# remote_v0_9_a8132eb9.net
KiCad netlist of a schematic drawn in EAGLE
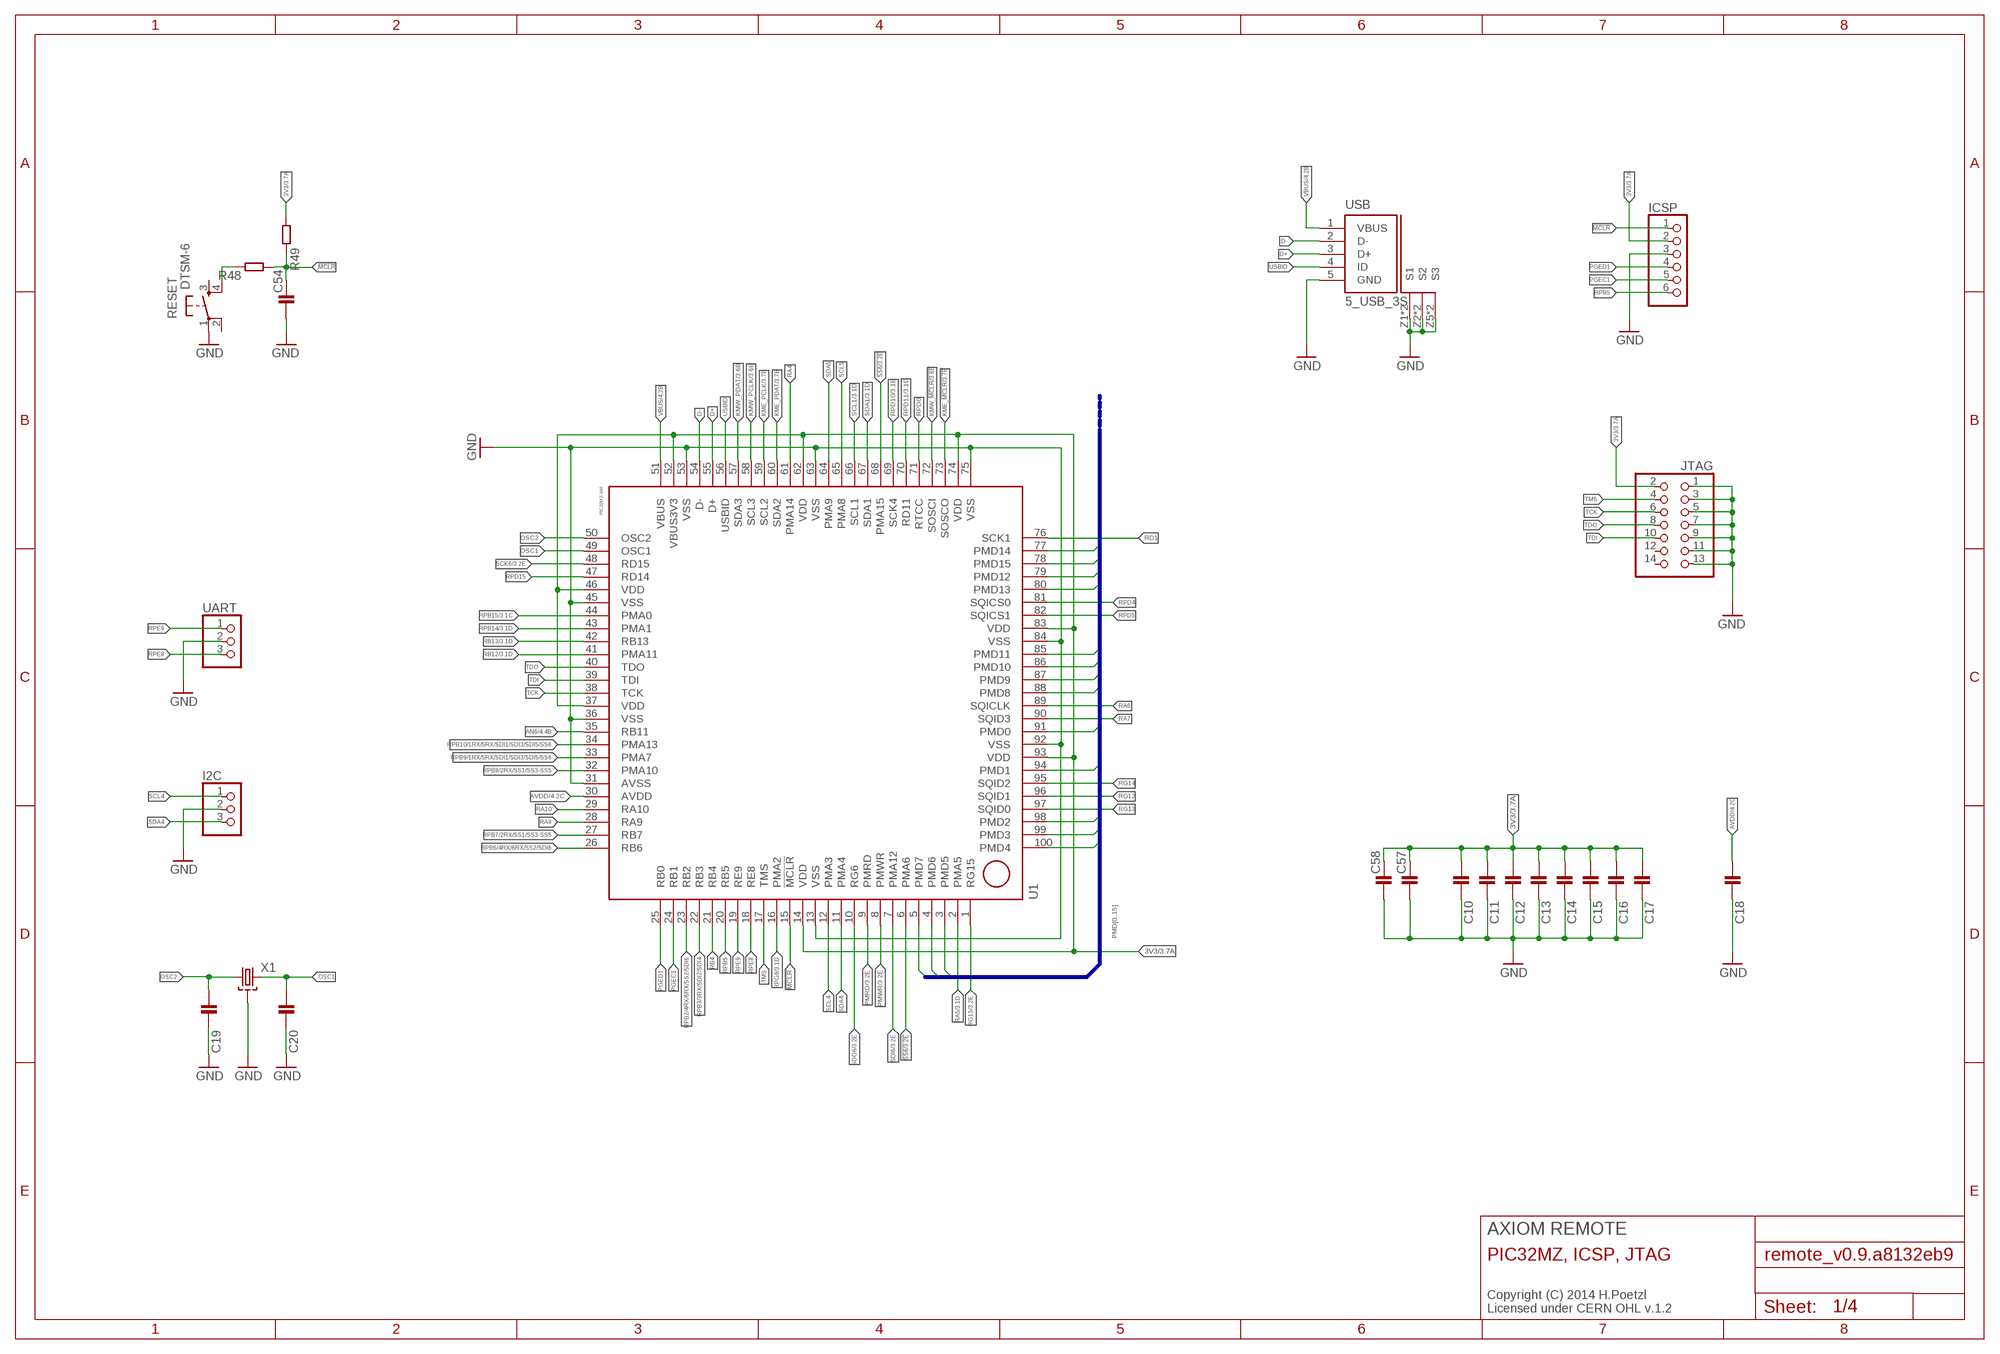
[diagram p0: schematic, sheet 1]
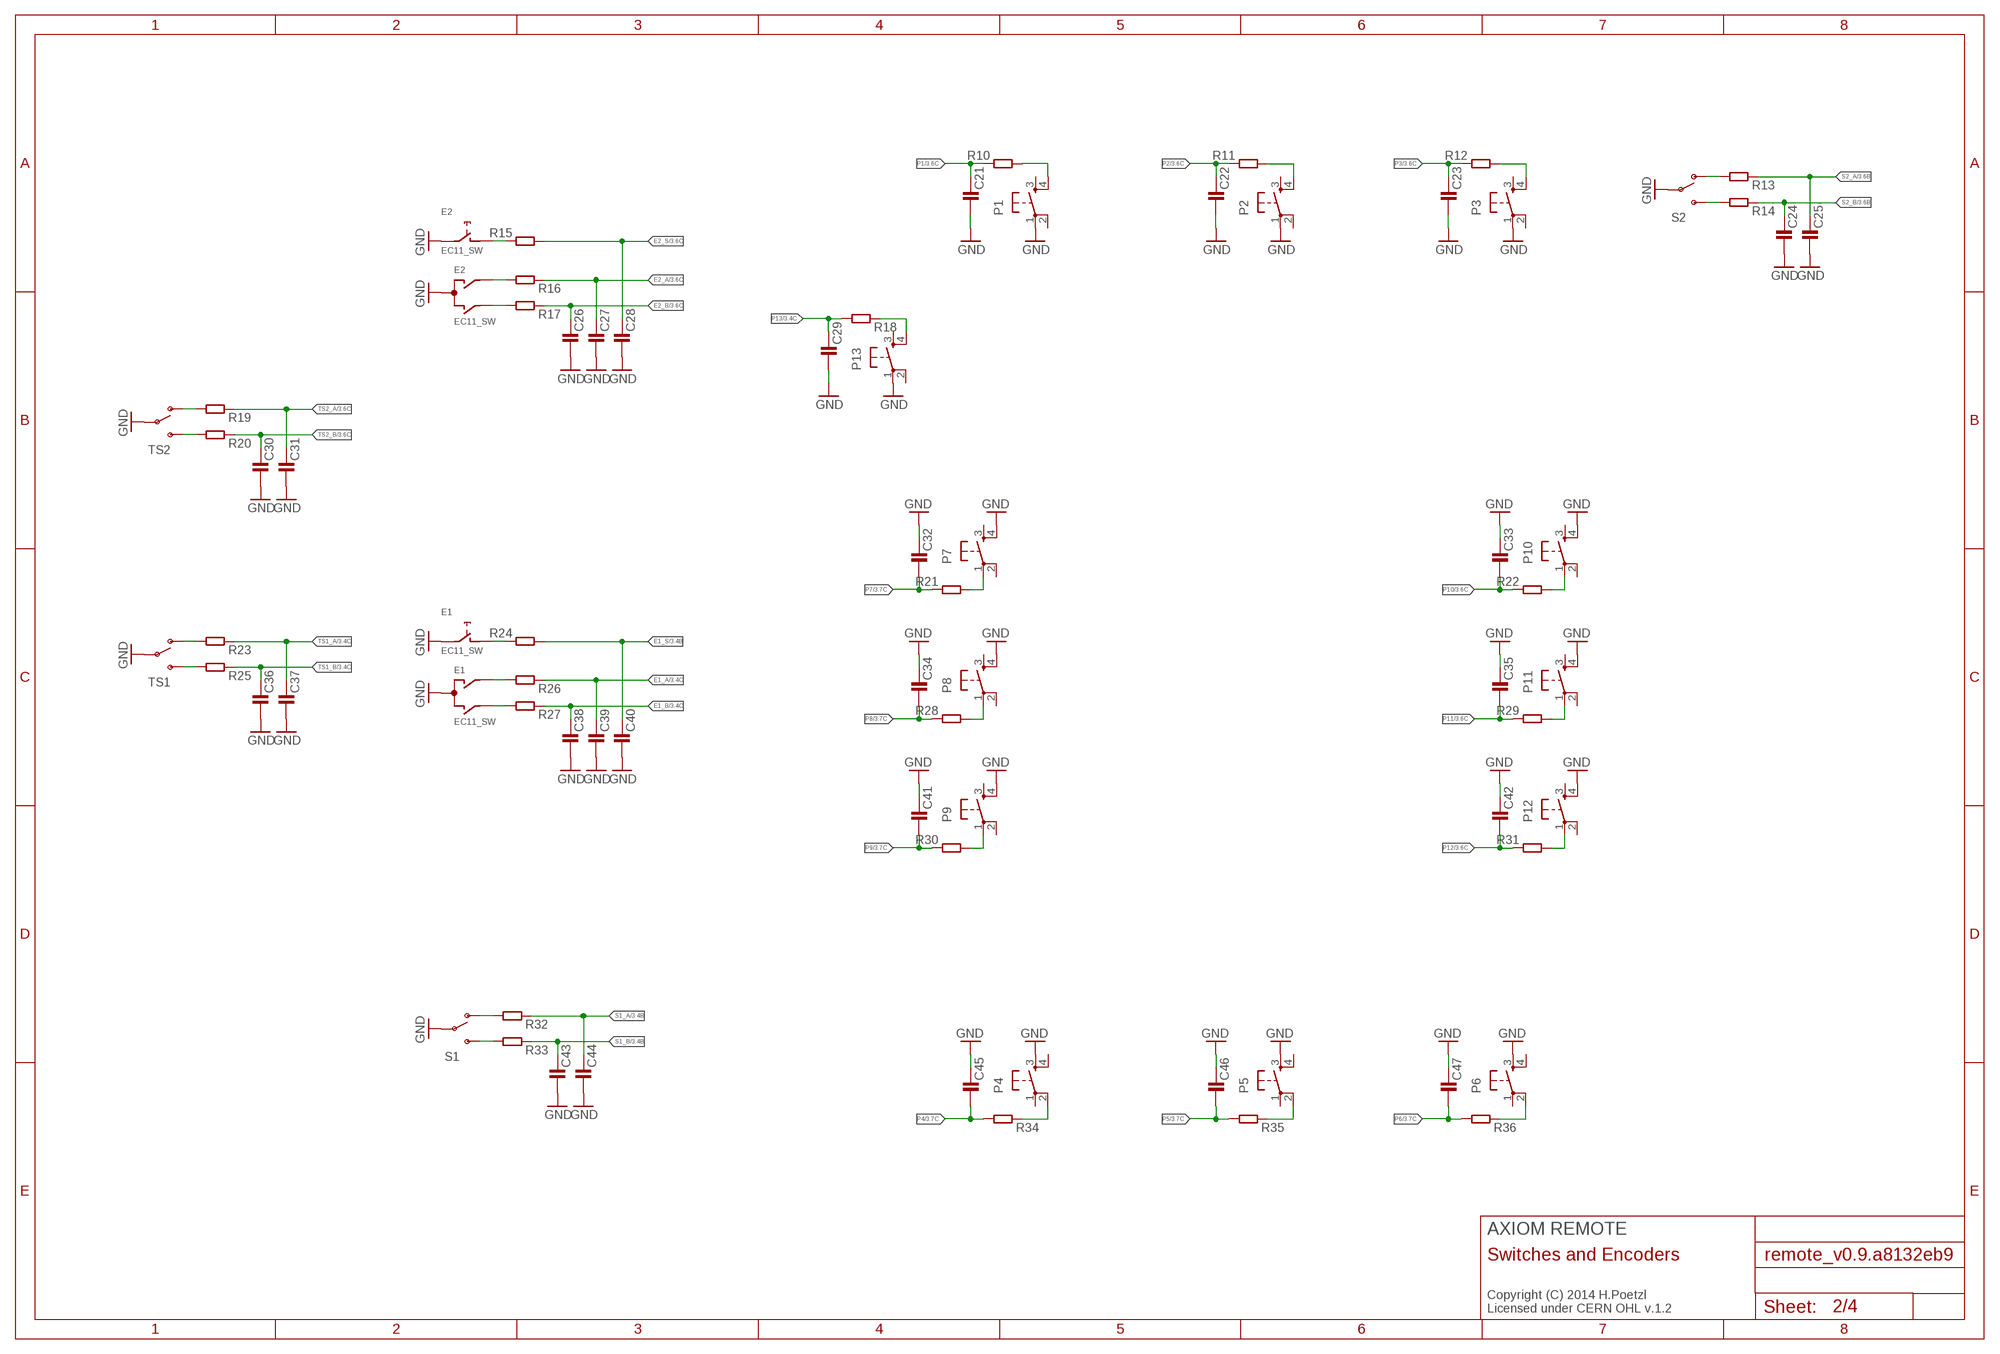
[diagram p1: schematic, sheet 2]
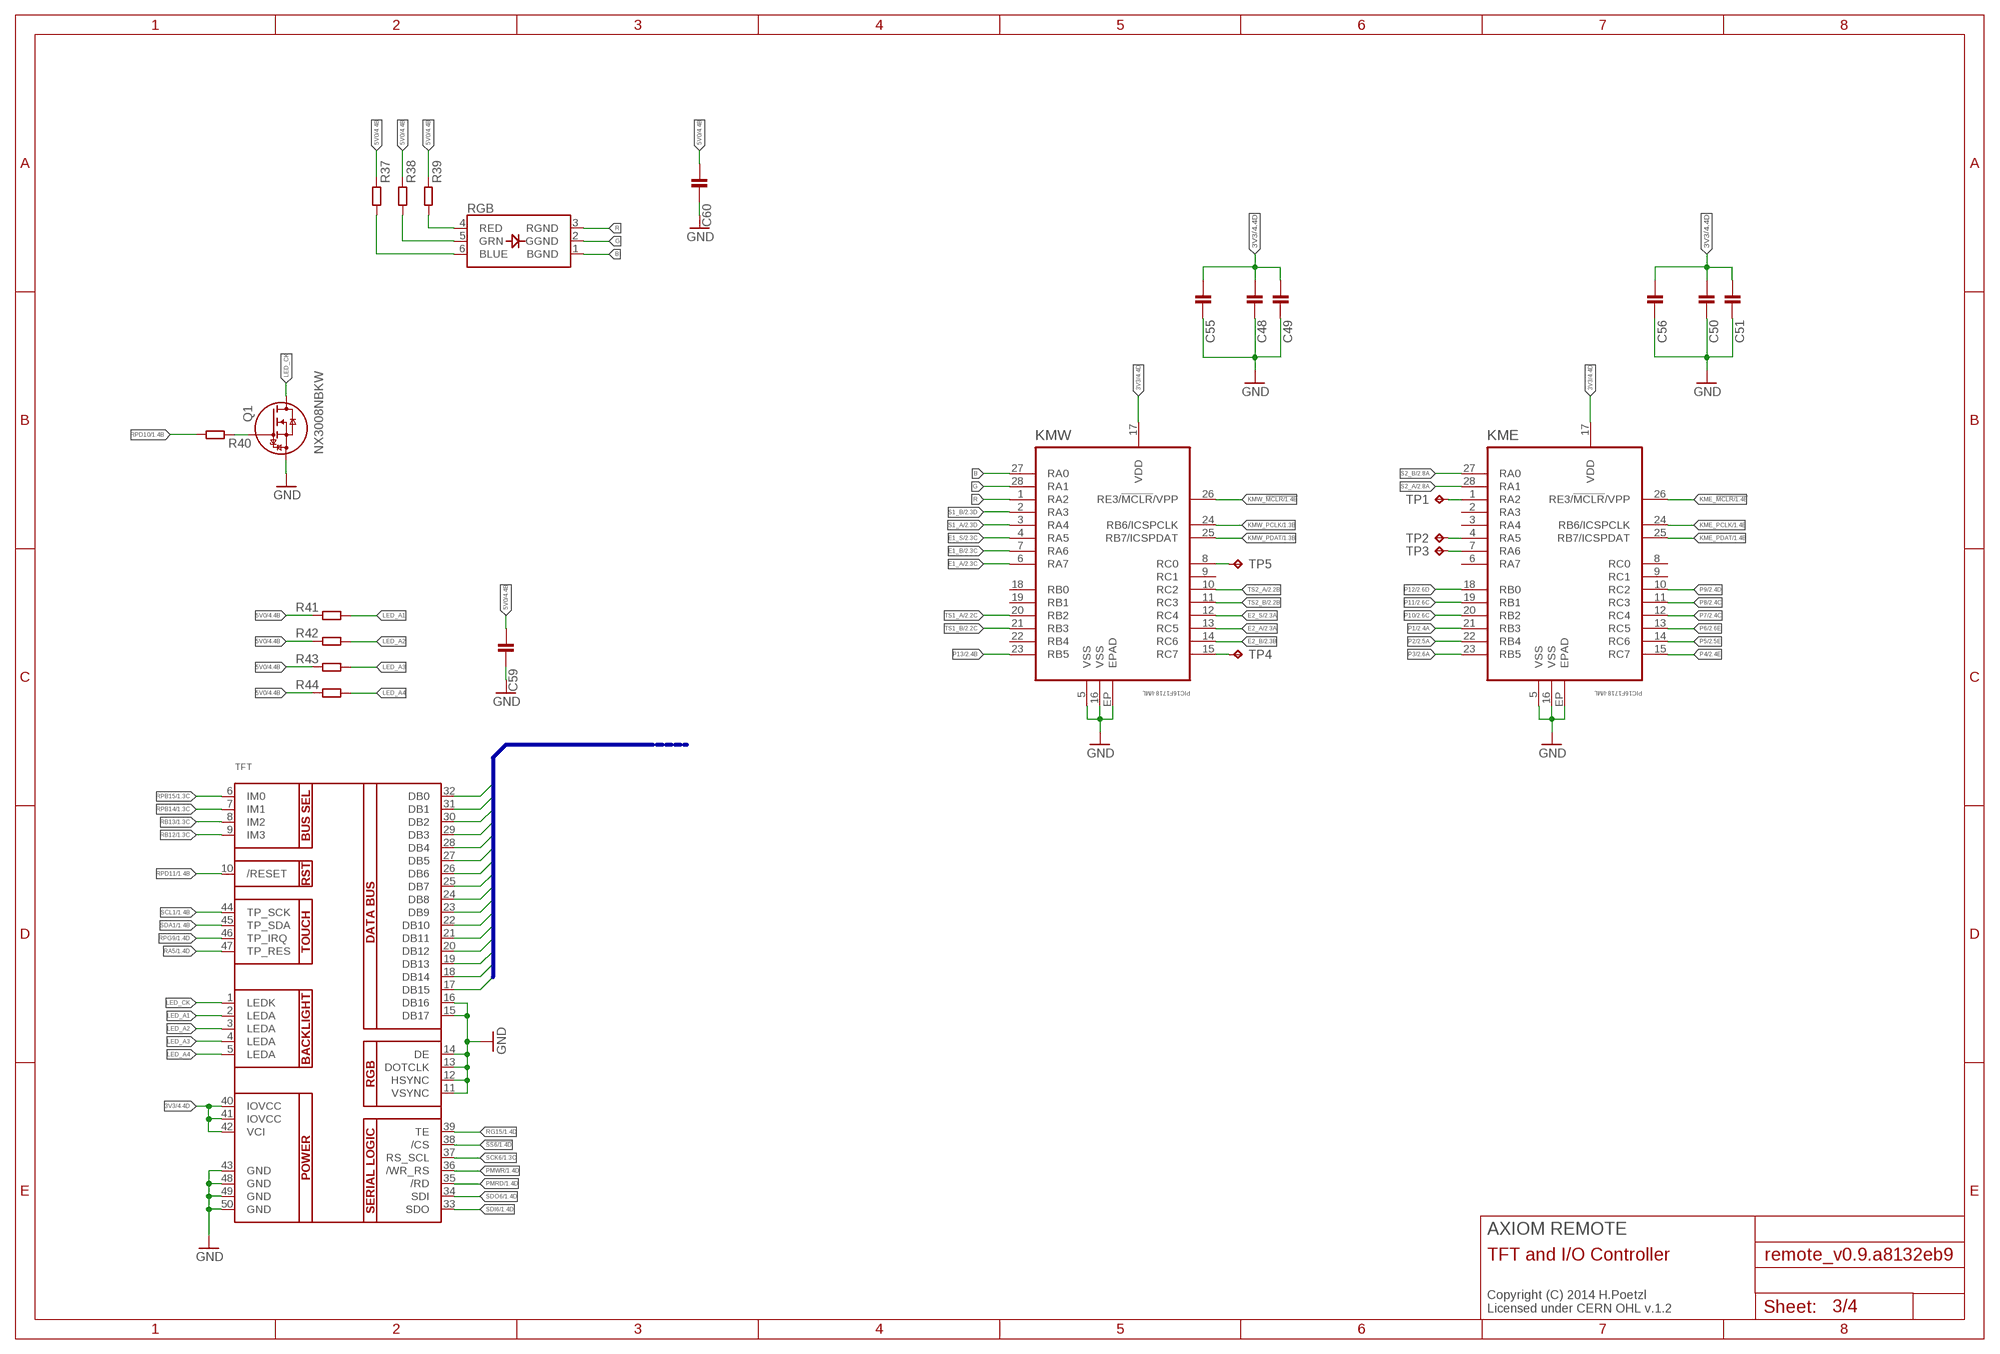
[diagram p2: schematic, sheet 3]
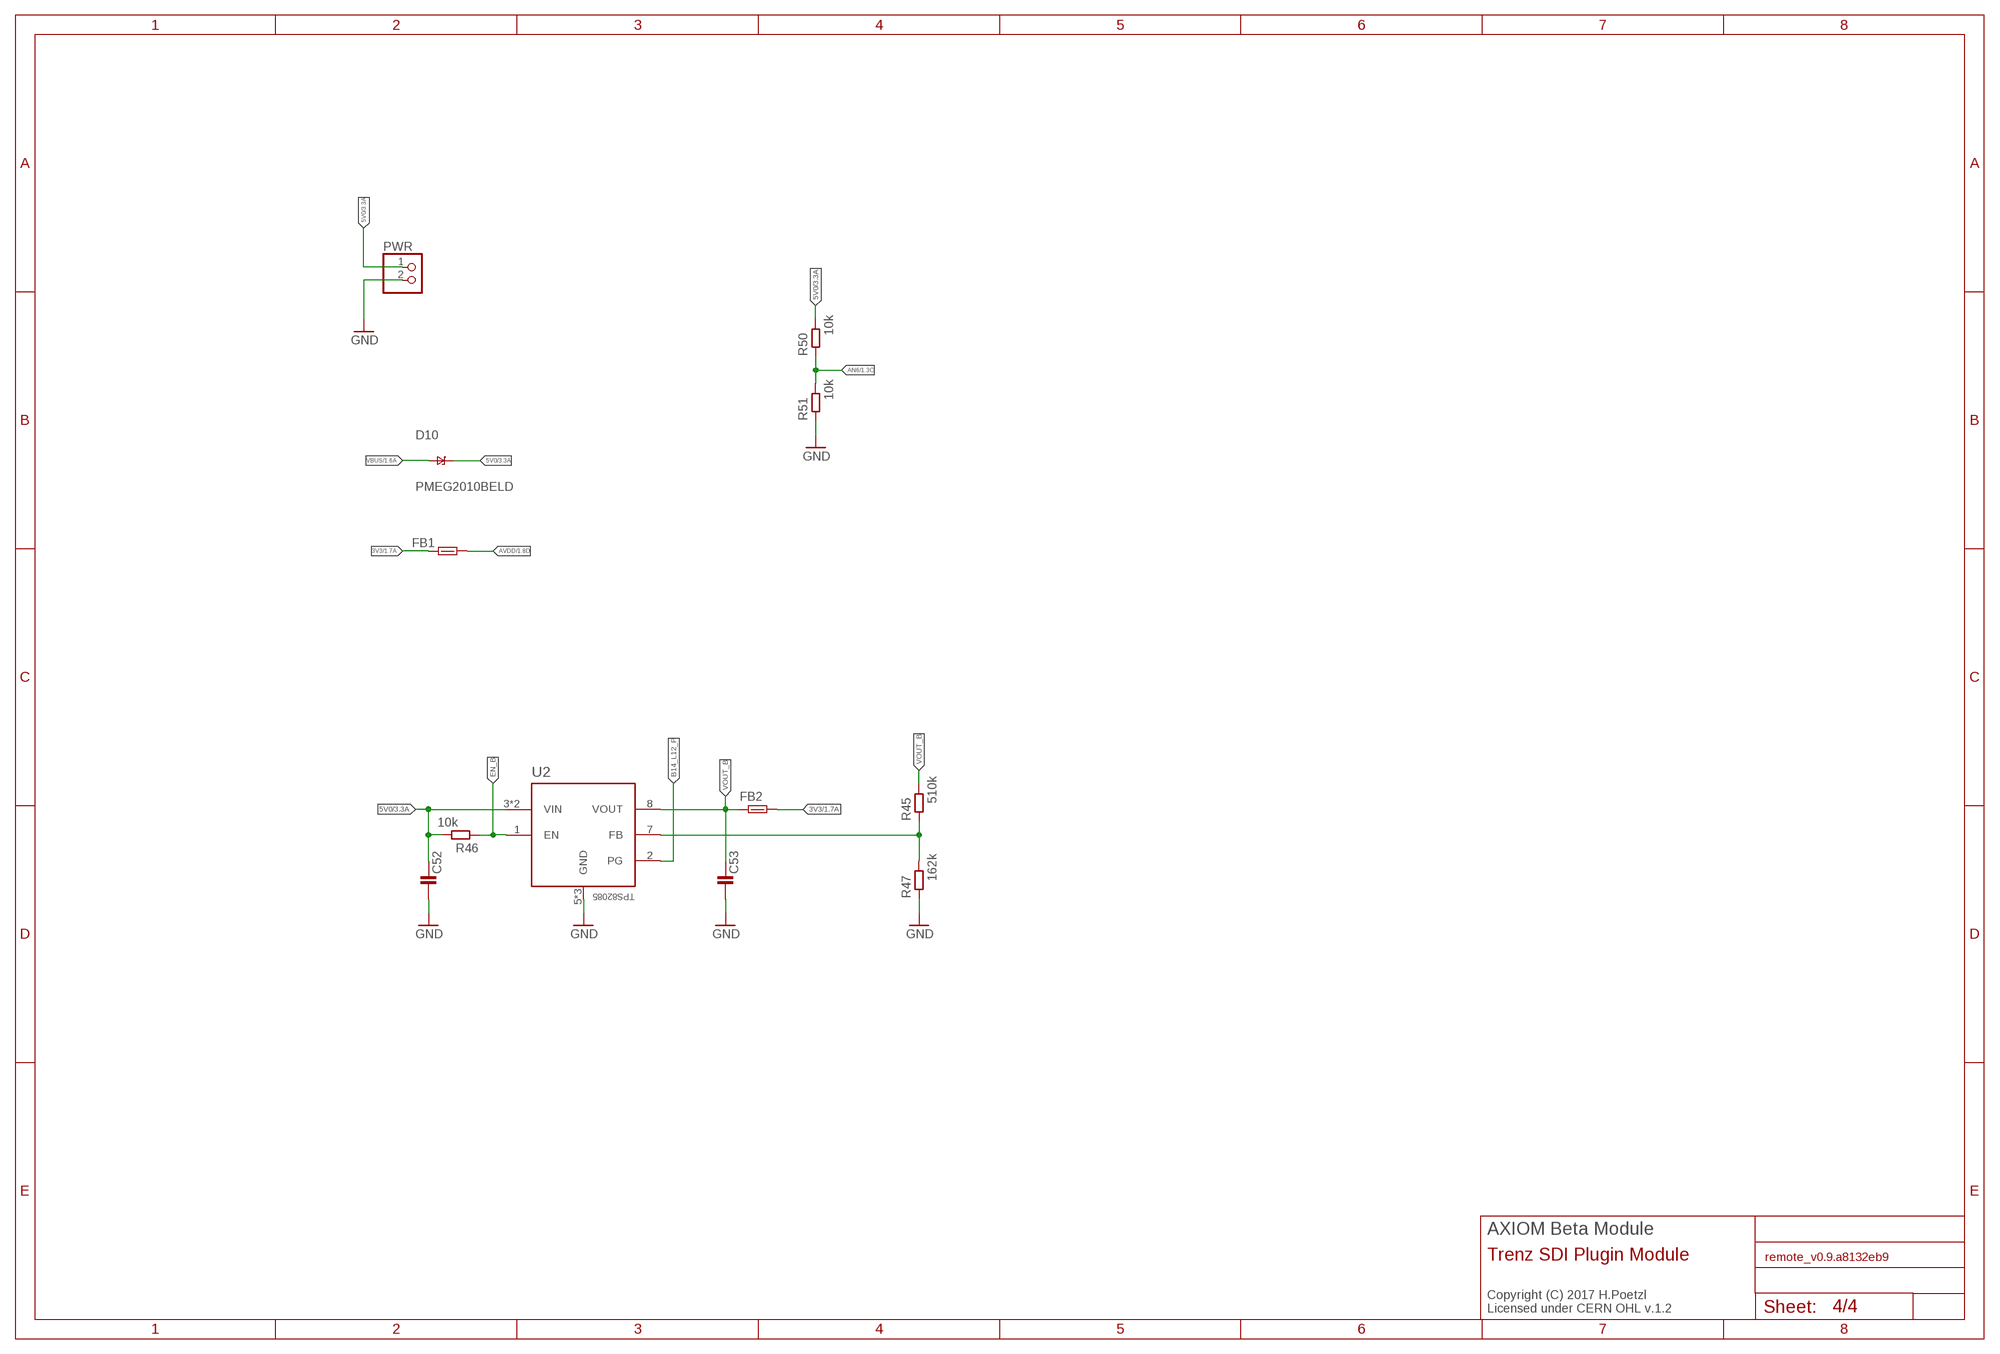
[diagram p3: schematic, sheet 4]

(export (version "E")
  (design (tool "Eeschema 10.0.6"))
  (components
    (comp (ref "C52")
      (value "C0603-C")
      (footprint "eagle-import:0603-C")
      (libsource (lib "eagle-import") (part "C0603-C"))
    )
    (comp (ref "C53")
      (value "C0603-C")
      (footprint "eagle-import:0603-C")
      (libsource (lib "eagle-import") (part "C0603-C"))
    )
    (comp (ref "D10")
      (value "PMEG2010BELD")
      (footprint "eagle-import:DFN1006D-2")
      (libsource (lib "eagle-import") (part "PMEG2010BELD"))
    )
    (comp (ref "FB1")
      (value "FB0402-C")
      (footprint "eagle-import:0402-C")
      (libsource (lib "eagle-import") (part "FB0402-C"))
    )
    (comp (ref "FB2")
      (value "FB0603-C")
      (footprint "eagle-import:0603-C")
      (libsource (lib "eagle-import") (part "FB0603-C"))
    )
    (comp (ref "PWR")
      (value "PINHD-1X02_2.54-90°")
      (footprint "eagle-import:1X02_90")
      (libsource (lib "eagle-import") (part "PINHD-1X02_2.54-90°"))
    )
    (comp (ref "R45")
      (value "510k")
      (footprint "eagle-import:0201-C")
      (libsource (lib "eagle-import") (part "R0201-C"))
    )
    (comp (ref "R46")
      (value "10k")
      (footprint "eagle-import:0201-C")
      (libsource (lib "eagle-import") (part "R0201-C"))
    )
    (comp (ref "R47")
      (value "162k")
      (footprint "eagle-import:0201-C")
      (libsource (lib "eagle-import") (part "R0201-C"))
    )
    (comp (ref "R50")
      (value "10k")
      (footprint "eagle-import:0402-C")
      (libsource (lib "eagle-import") (part "R0402-C"))
    )
    (comp (ref "R51")
      (value "10k")
      (footprint "eagle-import:0402-C")
      (libsource (lib "eagle-import") (part "R0402-C"))
    )
    (comp (ref "U2")
      (value "TPS82085")
      (footprint "eagle-import:MICROSIP")
      (libsource (lib "eagle-import") (part "TPS82085"))
    )
    (comp (ref "C10")
      (value "100n")
      (footprint "eagle-import:0402-C")
      (libsource (lib "eagle-import") (part "C0402-C"))
    )
    (comp (ref "C11")
      (value "100n")
      (footprint "eagle-import:0402-C")
      (libsource (lib "eagle-import") (part "C0402-C"))
    )
    (comp (ref "C12")
      (value "100n")
      (footprint "eagle-import:0402-C")
      (libsource (lib "eagle-import") (part "C0402-C"))
    )
    (comp (ref "C13")
      (value "100n")
      (footprint "eagle-import:0402-C")
      (libsource (lib "eagle-import") (part "C0402-C"))
    )
    (comp (ref "C14")
      (value "100n")
      (footprint "eagle-import:0402-C")
      (libsource (lib "eagle-import") (part "C0402-C"))
    )
    (comp (ref "C15")
      (value "100n")
      (footprint "eagle-import:0402-C")
      (libsource (lib "eagle-import") (part "C0402-C"))
    )
    (comp (ref "C16")
      (value "100n")
      (footprint "eagle-import:0402-C")
      (libsource (lib "eagle-import") (part "C0402-C"))
    )
    (comp (ref "C17")
      (value "100n")
      (footprint "eagle-import:0402-C")
      (libsource (lib "eagle-import") (part "C0402-C"))
    )
    (comp (ref "C18")
      (value "100n")
      (footprint "eagle-import:0402-C")
      (libsource (lib "eagle-import") (part "C0402-C"))
    )
    (comp (ref "C19")
      (value "100n")
      (footprint "eagle-import:0402-C")
      (libsource (lib "eagle-import") (part "C0402-C"))
    )
    (comp (ref "C20")
      (value "100n")
      (footprint "eagle-import:0402-C")
      (libsource (lib "eagle-import") (part "C0402-C"))
    )
    (comp (ref "C54")
      (value "C0402-C")
      (footprint "eagle-import:0402-C")
      (libsource (lib "eagle-import") (part "C0402-C"))
    )
    (comp (ref "C57")
      (value "C0805-C")
      (footprint "eagle-import:0805-C")
      (libsource (lib "eagle-import") (part "C0805-C"))
    )
    (comp (ref "C58")
      (value "C0805-C")
      (footprint "eagle-import:0805-C")
      (libsource (lib "eagle-import") (part "C0805-C"))
    )
    (comp (ref "I2C")
      (value "PINHD-1X03_2.54-90°")
      (footprint "eagle-import:1X03_90")
      (libsource (lib "eagle-import") (part "PINHD-1X03_2.54-90°"))
    )
    (comp (ref "ICSP")
      (value "PINHD-1X6/90")
      (footprint "eagle-import:1X06_90")
      (libsource (lib "eagle-import") (part "PINHD-1X6/90"))
    )
    (comp (ref "JTAG")
      (value "PINHD-2X07_2.00")
      (footprint "eagle-import:2X07M")
      (libsource (lib "eagle-import") (part "PINHD-2X07_2.00"))
    )
    (comp (ref "R48")
      (value "R0402-C")
      (footprint "eagle-import:0402-C")
      (libsource (lib "eagle-import") (part "R0402-C"))
    )
    (comp (ref "R49")
      (value "R0402-C")
      (footprint "eagle-import:0402-C")
      (libsource (lib "eagle-import") (part "R0402-C"))
    )
    (comp (ref "RESET")
      (value "DTSM-6")
      (footprint "eagle-import:3X4MM")
      (libsource (lib "eagle-import") (part "DTSM-6"))
    )
    (comp (ref "U1")
      (value "PIC32MZ-100")
      (footprint "eagle-import:QFP40P1400X1400X120-100N")
      (libsource (lib "eagle-import") (part "PIC32MZ-100"))
    )
    (comp (ref "UART")
      (value "PINHD-1X03_2.54-90°")
      (footprint "eagle-import:1X03_90")
      (libsource (lib "eagle-import") (part "PINHD-1X03_2.54-90°"))
    )
    (comp (ref "USB")
      (value "5_USB_3S")
      (footprint "eagle-import:MICRO-AB-H-SMT")
      (libsource (lib "eagle-import") (part "5_USB_3S"))
    )
    (comp (ref "X1")
      (value "SMD-4P-2G-2.0X1.6")
      (footprint "eagle-import:2.0X1.6")
      (libsource (lib "eagle-import") (part "SMD-4P-2G-2.0X1.6"))
    )
    (comp (ref "C21")
      (value "C0402-C")
      (footprint "eagle-import:0402-C")
      (libsource (lib "eagle-import") (part "C0402-C"))
    )
    (comp (ref "C22")
      (value "C0402-C")
      (footprint "eagle-import:0402-C")
      (libsource (lib "eagle-import") (part "C0402-C"))
    )
    (comp (ref "C23")
      (value "C0402-C")
      (footprint "eagle-import:0402-C")
      (libsource (lib "eagle-import") (part "C0402-C"))
    )
    (comp (ref "C24")
      (value "C0402-C")
      (footprint "eagle-import:0402-C")
      (libsource (lib "eagle-import") (part "C0402-C"))
    )
    (comp (ref "C25")
      (value "C0402-C")
      (footprint "eagle-import:0402-C")
      (libsource (lib "eagle-import") (part "C0402-C"))
    )
    (comp (ref "C26")
      (value "C0402-C")
      (footprint "eagle-import:0402-C")
      (libsource (lib "eagle-import") (part "C0402-C"))
    )
    (comp (ref "C27")
      (value "C0402-C")
      (footprint "eagle-import:0402-C")
      (libsource (lib "eagle-import") (part "C0402-C"))
    )
    (comp (ref "C28")
      (value "C0402-C")
      (footprint "eagle-import:0402-C")
      (libsource (lib "eagle-import") (part "C0402-C"))
    )
    (comp (ref "C29")
      (value "C0402-C")
      (footprint "eagle-import:0402-C")
      (libsource (lib "eagle-import") (part "C0402-C"))
    )
    (comp (ref "C30")
      (value "C0402-C")
      (footprint "eagle-import:0402-C")
      (libsource (lib "eagle-import") (part "C0402-C"))
    )
    (comp (ref "C31")
      (value "C0402-C")
      (footprint "eagle-import:0402-C")
      (libsource (lib "eagle-import") (part "C0402-C"))
    )
    (comp (ref "C32")
      (value "C0402-C")
      (footprint "eagle-import:0402-C")
      (libsource (lib "eagle-import") (part "C0402-C"))
    )
    (comp (ref "C33")
      (value "C0402-C")
      (footprint "eagle-import:0402-C")
      (libsource (lib "eagle-import") (part "C0402-C"))
    )
    (comp (ref "C34")
      (value "C0402-C")
      (footprint "eagle-import:0402-C")
      (libsource (lib "eagle-import") (part "C0402-C"))
    )
    (comp (ref "C35")
      (value "C0402-C")
      (footprint "eagle-import:0402-C")
      (libsource (lib "eagle-import") (part "C0402-C"))
    )
    (comp (ref "C36")
      (value "C0402-C")
      (footprint "eagle-import:0402-C")
      (libsource (lib "eagle-import") (part "C0402-C"))
    )
    (comp (ref "C37")
      (value "C0402-C")
      (footprint "eagle-import:0402-C")
      (libsource (lib "eagle-import") (part "C0402-C"))
    )
    (comp (ref "C38")
      (value "C0402-C")
      (footprint "eagle-import:0402-C")
      (libsource (lib "eagle-import") (part "C0402-C"))
    )
    (comp (ref "C39")
      (value "C0402-C")
      (footprint "eagle-import:0402-C")
      (libsource (lib "eagle-import") (part "C0402-C"))
    )
    (comp (ref "C40")
      (value "C0402-C")
      (footprint "eagle-import:0402-C")
      (libsource (lib "eagle-import") (part "C0402-C"))
    )
    (comp (ref "C41")
      (value "C0402-C")
      (footprint "eagle-import:0402-C")
      (libsource (lib "eagle-import") (part "C0402-C"))
    )
    (comp (ref "C42")
      (value "C0402-C")
      (footprint "eagle-import:0402-C")
      (libsource (lib "eagle-import") (part "C0402-C"))
    )
    (comp (ref "C43")
      (value "C0402-C")
      (footprint "eagle-import:0402-C")
      (libsource (lib "eagle-import") (part "C0402-C"))
    )
    (comp (ref "C44")
      (value "C0402-C")
      (footprint "eagle-import:0402-C")
      (libsource (lib "eagle-import") (part "C0402-C"))
    )
    (comp (ref "C45")
      (value "C0402-C")
      (footprint "eagle-import:0402-C")
      (libsource (lib "eagle-import") (part "C0402-C"))
    )
    (comp (ref "C46")
      (value "C0402-C")
      (footprint "eagle-import:0402-C")
      (libsource (lib "eagle-import") (part "C0402-C"))
    )
    (comp (ref "C47")
      (value "C0402-C")
      (footprint "eagle-import:0402-C")
      (libsource (lib "eagle-import") (part "C0402-C"))
    )
    (comp (ref "E1")
      (value "EC11_SW")
      (footprint "eagle-import:EC11_SW")
      (libsource (lib "eagle-import") (part "EC11_SW"))
    )
    (comp (ref "E2")
      (value "EC11_SW")
      (footprint "eagle-import:EC11_SW")
      (libsource (lib "eagle-import") (part "EC11_SW"))
    )
    (comp (ref "P1")
      (value "DTSM-6THT")
      (footprint "eagle-import:6X6-THT")
      (libsource (lib "eagle-import") (part "DTSM-6THT"))
    )
    (comp (ref "P2")
      (value "DTSM-6THT")
      (footprint "eagle-import:6X6-THT")
      (libsource (lib "eagle-import") (part "DTSM-6THT"))
    )
    (comp (ref "P3")
      (value "DTSM-6THT")
      (footprint "eagle-import:6X6-THT")
      (libsource (lib "eagle-import") (part "DTSM-6THT"))
    )
    (comp (ref "P4")
      (value "DTSM-6THT")
      (footprint "eagle-import:6X6-THT")
      (libsource (lib "eagle-import") (part "DTSM-6THT"))
    )
    (comp (ref "P5")
      (value "DTSM-6THT")
      (footprint "eagle-import:6X6-THT")
      (libsource (lib "eagle-import") (part "DTSM-6THT"))
    )
    (comp (ref "P6")
      (value "DTSM-6THT")
      (footprint "eagle-import:6X6-THT")
      (libsource (lib "eagle-import") (part "DTSM-6THT"))
    )
    (comp (ref "P7")
      (value "DTSM-6THT")
      (footprint "eagle-import:6X6-THT")
      (libsource (lib "eagle-import") (part "DTSM-6THT"))
    )
    (comp (ref "P8")
      (value "DTSM-6THT")
      (footprint "eagle-import:6X6-THT")
      (libsource (lib "eagle-import") (part "DTSM-6THT"))
    )
    (comp (ref "P9")
      (value "DTSM-6THT")
      (footprint "eagle-import:6X6-THT")
      (libsource (lib "eagle-import") (part "DTSM-6THT"))
    )
    (comp (ref "P10")
      (value "DTSM-6THT")
      (footprint "eagle-import:6X6-THT")
      (libsource (lib "eagle-import") (part "DTSM-6THT"))
    )
    (comp (ref "P11")
      (value "DTSM-6THT")
      (footprint "eagle-import:6X6-THT")
      (libsource (lib "eagle-import") (part "DTSM-6THT"))
    )
    (comp (ref "P12")
      (value "DTSM-6THT")
      (footprint "eagle-import:6X6-THT")
      (libsource (lib "eagle-import") (part "DTSM-6THT"))
    )
    (comp (ref "P13")
      (value "DTSM-6THT")
      (footprint "eagle-import:6X6-THT")
      (libsource (lib "eagle-import") (part "DTSM-6THT"))
    )
    (comp (ref "R10")
      (value "R0402-C")
      (footprint "eagle-import:0402-C")
      (libsource (lib "eagle-import") (part "R0402-C"))
    )
    (comp (ref "R11")
      (value "R0402-C")
      (footprint "eagle-import:0402-C")
      (libsource (lib "eagle-import") (part "R0402-C"))
    )
    (comp (ref "R12")
      (value "R0402-C")
      (footprint "eagle-import:0402-C")
      (libsource (lib "eagle-import") (part "R0402-C"))
    )
    (comp (ref "R13")
      (value "R0402-C")
      (footprint "eagle-import:0402-C")
      (libsource (lib "eagle-import") (part "R0402-C"))
    )
    (comp (ref "R14")
      (value "R0402-C")
      (footprint "eagle-import:0402-C")
      (libsource (lib "eagle-import") (part "R0402-C"))
    )
    (comp (ref "R15")
      (value "R0402-C")
      (footprint "eagle-import:0402-C")
      (libsource (lib "eagle-import") (part "R0402-C"))
    )
    (comp (ref "R16")
      (value "R0402-C")
      (footprint "eagle-import:0402-C")
      (libsource (lib "eagle-import") (part "R0402-C"))
    )
    (comp (ref "R17")
      (value "R0402-C")
      (footprint "eagle-import:0402-C")
      (libsource (lib "eagle-import") (part "R0402-C"))
    )
    (comp (ref "R18")
      (value "R0402-C")
      (footprint "eagle-import:0402-C")
      (libsource (lib "eagle-import") (part "R0402-C"))
    )
    (comp (ref "R19")
      (value "R0402-C")
      (footprint "eagle-import:0402-C")
      (libsource (lib "eagle-import") (part "R0402-C"))
    )
    (comp (ref "R20")
      (value "R0402-C")
      (footprint "eagle-import:0402-C")
      (libsource (lib "eagle-import") (part "R0402-C"))
    )
    (comp (ref "R21")
      (value "R0402-C")
      (footprint "eagle-import:0402-C")
      (libsource (lib "eagle-import") (part "R0402-C"))
    )
    (comp (ref "R22")
      (value "R0402-C")
      (footprint "eagle-import:0402-C")
      (libsource (lib "eagle-import") (part "R0402-C"))
    )
    (comp (ref "R23")
      (value "R0402-C")
      (footprint "eagle-import:0402-C")
      (libsource (lib "eagle-import") (part "R0402-C"))
    )
    (comp (ref "R24")
      (value "R0402-C")
      (footprint "eagle-import:0402-C")
      (libsource (lib "eagle-import") (part "R0402-C"))
    )
    (comp (ref "R25")
      (value "R0402-C")
      (footprint "eagle-import:0402-C")
      (libsource (lib "eagle-import") (part "R0402-C"))
    )
    (comp (ref "R26")
      (value "R0402-C")
      (footprint "eagle-import:0402-C")
      (libsource (lib "eagle-import") (part "R0402-C"))
    )
    (comp (ref "R27")
      (value "R0402-C")
      (footprint "eagle-import:0402-C")
      (libsource (lib "eagle-import") (part "R0402-C"))
    )
    (comp (ref "R28")
      (value "R0402-C")
      (footprint "eagle-import:0402-C")
      (libsource (lib "eagle-import") (part "R0402-C"))
    )
    (comp (ref "R29")
      (value "R0402-C")
      (footprint "eagle-import:0402-C")
      (libsource (lib "eagle-import") (part "R0402-C"))
    )
    (comp (ref "R30")
      (value "R0402-C")
      (footprint "eagle-import:0402-C")
      (libsource (lib "eagle-import") (part "R0402-C"))
    )
    (comp (ref "R31")
      (value "R0402-C")
      (footprint "eagle-import:0402-C")
      (libsource (lib "eagle-import") (part "R0402-C"))
    )
    (comp (ref "R32")
      (value "R0402-C")
      (footprint "eagle-import:0402-C")
      (libsource (lib "eagle-import") (part "R0402-C"))
    )
    (comp (ref "R33")
      (value "R0402-C")
      (footprint "eagle-import:0402-C")
      (libsource (lib "eagle-import") (part "R0402-C"))
    )
    (comp (ref "R34")
      (value "R0402-C")
      (footprint "eagle-import:0402-C")
      (libsource (lib "eagle-import") (part "R0402-C"))
    )
    (comp (ref "R35")
      (value "R0402-C")
      (footprint "eagle-import:0402-C")
      (libsource (lib "eagle-import") (part "R0402-C"))
    )
    (comp (ref "R36")
      (value "R0402-C")
      (footprint "eagle-import:0402-C")
      (libsource (lib "eagle-import") (part "R0402-C"))
    )
    (comp (ref "S1")
      (value "SWITCH-SPDTTHT")
      (footprint "eagle-import:1101M2S3CBE2")
      (libsource (lib "eagle-import") (part "SWITCH-SPDTTHT"))
    )
    (comp (ref "S2")
      (value "SWITCH-SPDTTHT-RA")
      (footprint "eagle-import:1101M2S3ABE2")
      (libsource (lib "eagle-import") (part "SWITCH-SPDTTHT-RA"))
    )
    (comp (ref "TS1")
      (value "SWITCH-SPDTSTG-RA")
      (footprint "eagle-import:200SPXTXBXM6")
      (libsource (lib "eagle-import") (part "SWITCH-SPDTSTG-RA"))
    )
    (comp (ref "TS2")
      (value "SWITCH-SPDTSTG-RA")
      (footprint "eagle-import:200SPXTXBXM6")
      (libsource (lib "eagle-import") (part "SWITCH-SPDTSTG-RA"))
    )
    (comp (ref "C48")
      (value "100n")
      (footprint "eagle-import:0402-C")
      (libsource (lib "eagle-import") (part "C0402-C"))
    )
    (comp (ref "C49")
      (value "100n")
      (footprint "eagle-import:0402-C")
      (libsource (lib "eagle-import") (part "C0402-C"))
    )
    (comp (ref "C50")
      (value "100n")
      (footprint "eagle-import:0402-C")
      (libsource (lib "eagle-import") (part "C0402-C"))
    )
    (comp (ref "C51")
      (value "100n")
      (footprint "eagle-import:0402-C")
      (libsource (lib "eagle-import") (part "C0402-C"))
    )
    (comp (ref "C55")
      (value "100n")
      (footprint "eagle-import:0805-C")
      (libsource (lib "eagle-import") (part "C0805-C"))
    )
    (comp (ref "C56")
      (value "100n")
      (footprint "eagle-import:0805-C")
      (libsource (lib "eagle-import") (part "C0805-C"))
    )
    (comp (ref "C59")
      (value "100n")
      (footprint "eagle-import:0805-C")
      (libsource (lib "eagle-import") (part "C0805-C"))
    )
    (comp (ref "C60")
      (value "100n")
      (footprint "eagle-import:0805-C")
      (libsource (lib "eagle-import") (part "C0805-C"))
    )
    (comp (ref "KME")
      (value "PIC16F1718-I/ML")
      (footprint "eagle-import:QFN65P600X600X100-29N")
      (libsource (lib "eagle-import") (part "PIC16F1718-I/ML"))
    )
    (comp (ref "KMW")
      (value "PIC16F1718-I/ML")
      (footprint "eagle-import:QFN65P600X600X100-29N")
      (libsource (lib "eagle-import") (part "PIC16F1718-I/ML"))
    )
    (comp (ref "Q1")
      (value "NX3008NBKW")
      (footprint "eagle-import:SOT323")
      (libsource (lib "eagle-import") (part "NX3008NBKW"))
    )
    (comp (ref "R37")
      (value "R0603-C")
      (footprint "eagle-import:0603-C")
      (libsource (lib "eagle-import") (part "R0603-C"))
    )
    (comp (ref "R38")
      (value "R0603-C")
      (footprint "eagle-import:0603-C")
      (libsource (lib "eagle-import") (part "R0603-C"))
    )
    (comp (ref "R39")
      (value "R0603-C")
      (footprint "eagle-import:0603-C")
      (libsource (lib "eagle-import") (part "R0603-C"))
    )
    (comp (ref "R40")
      (value "R0402-C")
      (footprint "eagle-import:0402-C")
      (libsource (lib "eagle-import") (part "R0402-C"))
    )
    (comp (ref "R41")
      (value "R0805-C")
      (footprint "eagle-import:0805-C")
      (libsource (lib "eagle-import") (part "R0805-C"))
    )
    (comp (ref "R42")
      (value "R0805-C")
      (footprint "eagle-import:0805-C")
      (libsource (lib "eagle-import") (part "R0805-C"))
    )
    (comp (ref "R43")
      (value "R0805-C")
      (footprint "eagle-import:0805-C")
      (libsource (lib "eagle-import") (part "R0805-C"))
    )
    (comp (ref "R44")
      (value "R0805-C")
      (footprint "eagle-import:0805-C")
      (libsource (lib "eagle-import") (part "R0805-C"))
    )
    (comp (ref "RGB")
      (value "LED_RGB_PLCC6CREE-CLV6A")
      (footprint "eagle-import:RGBLED_PLCC6")
      (libsource (lib "eagle-import") (part "LED_RGB_PLCC6CREE-CLV6A"))
    )
    (comp (ref "TFT")
      (value "DISP_LCD_CTP28_SAMPLE")
      (footprint "eagle-import:TFT_2.83IN_240X320_50PIN")
      (libsource (lib "eagle-import") (part "DISP_LCD_CTP28_SAMPLE"))
    )
    (comp (ref "TP1")
      (value "TPTP12R")
      (footprint "eagle-import:TP12R")
      (libsource (lib "eagle-import") (part "TPTP12R"))
    )
    (comp (ref "TP2")
      (value "TPTP12R")
      (footprint "eagle-import:TP12R")
      (libsource (lib "eagle-import") (part "TPTP12R"))
    )
    (comp (ref "TP3")
      (value "TPTP12R")
      (footprint "eagle-import:TP12R")
      (libsource (lib "eagle-import") (part "TPTP12R"))
    )
    (comp (ref "TP4")
      (value "TPTP12R")
      (footprint "eagle-import:TP12R")
      (libsource (lib "eagle-import") (part "TPTP12R"))
    )
    (comp (ref "TP5")
      (value "TPTP12R")
      (footprint "eagle-import:TP12R")
      (libsource (lib "eagle-import") (part "TPTP12R"))
    )
  )
  (nets
    (net (code "2") (name "3V3") (class "Default")
      (node (ref "C10") (pin "1") (pinfunction "1_1") (pintype "passive"))
      (node (ref "C11") (pin "1") (pinfunction "1_1") (pintype "passive"))
      (node (ref "C12") (pin "1") (pinfunction "1_1") (pintype "passive"))
      (node (ref "C13") (pin "1") (pinfunction "1_1") (pintype "passive"))
      (node (ref "C14") (pin "1") (pinfunction "1_1") (pintype "passive"))
      (node (ref "C15") (pin "1") (pinfunction "1_1") (pintype "passive"))
      (node (ref "C16") (pin "1") (pinfunction "1_1") (pintype "passive"))
      (node (ref "C17") (pin "1") (pinfunction "1_1") (pintype "passive"))
      (node (ref "C48") (pin "1") (pinfunction "1_1") (pintype "passive"))
      (node (ref "C49") (pin "1") (pinfunction "1_1") (pintype "passive"))
      (node (ref "C50") (pin "1") (pinfunction "1_1") (pintype "passive"))
      (node (ref "C51") (pin "1") (pinfunction "1_1") (pintype "passive"))
      (node (ref "C55") (pin "1") (pinfunction "1_1") (pintype "passive"))
      (node (ref "C56") (pin "1") (pinfunction "1_1") (pintype "passive"))
      (node (ref "C57") (pin "1") (pinfunction "1_1") (pintype "passive"))
      (node (ref "C58") (pin "1") (pinfunction "1_1") (pintype "passive"))
      (node (ref "FB1") (pin "1") (pinfunction "1_1") (pintype "passive"))
      (node (ref "FB2") (pin "2") (pinfunction "2_2") (pintype "passive"))
      (node (ref "ICSP") (pin "2") (pinfunction "2_2") (pintype "passive"))
      (node (ref "JTAG") (pin "2") (pinfunction "2_2") (pintype "passive"))
      (node (ref "KME") (pin "17") (pinfunction "VDD_17") (pintype "power_in"))
      (node (ref "KMW") (pin "17") (pinfunction "VDD_17") (pintype "power_in"))
      (node (ref "R49") (pin "2") (pinfunction "2_2") (pintype "passive"))
      (node (ref "TFT") (pin "40") (pinfunction "IOVCC_40") (pintype "bidirectional"))
      (node (ref "TFT") (pin "41") (pinfunction "IOVCC_41") (pintype "bidirectional"))
      (node (ref "TFT") (pin "42") (pinfunction "VCI_42") (pintype "bidirectional"))
      (node (ref "U1") (pin "14") (pinfunction "VDD_14") (pintype "power_in"))
      (node (ref "U1") (pin "37") (pinfunction "VDD_37") (pintype "power_in"))
      (node (ref "U1") (pin "46") (pinfunction "VDD_46") (pintype "power_in"))
      (node (ref "U1") (pin "52") (pinfunction "VBUS3V3_52") (pintype "power_in"))
      (node (ref "U1") (pin "62") (pinfunction "VDD_62") (pintype "power_in"))
      (node (ref "U1") (pin "74") (pinfunction "VDD_74") (pintype "power_in"))
      (node (ref "U1") (pin "83") (pinfunction "VDD_83") (pintype "power_in"))
      (node (ref "U1") (pin "93") (pinfunction "VDD_93") (pintype "power_in"))
    )
    (net (code "3") (name "5V0") (class "Default")
      (node (ref "C52") (pin "1") (pinfunction "1_1") (pintype "passive"))
      (node (ref "C59") (pin "1") (pinfunction "1_1") (pintype "passive"))
      (node (ref "C60") (pin "1") (pinfunction "1_1") (pintype "passive"))
      (node (ref "D10") (pin "C") (pinfunction "K_C") (pintype "passive"))
      (node (ref "PWR") (pin "1") (pinfunction "1_1") (pintype "passive"))
      (node (ref "R37") (pin "1") (pinfunction "1_1") (pintype "passive"))
      (node (ref "R38") (pin "1") (pinfunction "1_1") (pintype "passive"))
      (node (ref "R39") (pin "1") (pinfunction "1_1") (pintype "passive"))
      (node (ref "R41") (pin "1") (pinfunction "1_1") (pintype "passive"))
      (node (ref "R42") (pin "1") (pinfunction "1_1") (pintype "passive"))
      (node (ref "R43") (pin "1") (pinfunction "1_1") (pintype "passive"))
      (node (ref "R44") (pin "1") (pinfunction "1_1") (pintype "passive"))
      (node (ref "R46") (pin "2") (pinfunction "2_2") (pintype "passive"))
      (node (ref "R50") (pin "2") (pinfunction "2_2") (pintype "passive"))
      (node (ref "U2") (pin "3") (pinfunction "VIN_3") (pintype "power_in"))
      (node (ref "U2") (pin "4") (pinfunction "VIN_4") (pintype "power_in"))
    )
    (net (code "4") (name "AN6") (class "Default")
      (node (ref "R50") (pin "1") (pinfunction "1_1") (pintype "passive"))
      (node (ref "R51") (pin "2") (pinfunction "2_2") (pintype "passive"))
      (node (ref "U1") (pin "35") (pinfunction "RB11_35") (pintype "bidirectional"))
    )
    (net (code "5") (name "AVDD") (class "Default")
      (node (ref "C18") (pin "1") (pinfunction "1_1") (pintype "passive"))
      (node (ref "FB1") (pin "2") (pinfunction "2_2") (pintype "passive"))
      (node (ref "U1") (pin "30") (pinfunction "AVDD_30") (pintype "power_in"))
    )
    (net (code "6") (name "B") (class "Default")
      (node (ref "KMW") (pin "27") (pinfunction "RA0_27") (pintype "bidirectional"))
      (node (ref "RGB") (pin "1") (pinfunction "BGND_1") (pintype "power_in"))
    )
    (net (code "7") (name "B14_L12_P") (class "Default")
      (node (ref "U2") (pin "2") (pinfunction "PG_2") (pintype "power_in"))
    )
    (net (code "8") (name "D+") (class "Default")
      (node (ref "U1") (pin "55") (pinfunction "D+_55") (pintype "bidirectional"))
      (node (ref "USB") (pin "3") (pinfunction "D+_3") (pintype "passive"))
    )
    (net (code "9") (name "D-") (class "Default")
      (node (ref "U1") (pin "54") (pinfunction "D-_54") (pintype "bidirectional"))
      (node (ref "USB") (pin "2") (pinfunction "D-_2") (pintype "passive"))
    )
    (net (code "10") (name "E1_A") (class "Default")
      (node (ref "C39") (pin "1") (pinfunction "1_1") (pintype "passive"))
      (node (ref "KMW") (pin "6") (pinfunction "RA7_6") (pintype "bidirectional"))
      (node (ref "R26") (pin "1") (pinfunction "1_1") (pintype "passive"))
    )
    (net (code "11") (name "E1_B") (class "Default")
      (node (ref "C38") (pin "1") (pinfunction "1_1") (pintype "passive"))
      (node (ref "KMW") (pin "7") (pinfunction "RA6_7") (pintype "bidirectional"))
      (node (ref "R27") (pin "1") (pinfunction "1_1") (pintype "passive"))
    )
    (net (code "12") (name "E1_S") (class "Default")
      (node (ref "C40") (pin "1") (pinfunction "1_1") (pintype "passive"))
      (node (ref "KMW") (pin "4") (pinfunction "RA5_4") (pintype "bidirectional"))
      (node (ref "R24") (pin "2") (pinfunction "2_2") (pintype "passive"))
    )
    (net (code "13") (name "E2_A") (class "Default")
      (node (ref "C27") (pin "1") (pinfunction "1_1") (pintype "passive"))
      (node (ref "KMW") (pin "13") (pinfunction "RC5_13") (pintype "bidirectional"))
      (node (ref "R16") (pin "1") (pinfunction "1_1") (pintype "passive"))
    )
    (net (code "14") (name "E2_B") (class "Default")
      (node (ref "C26") (pin "1") (pinfunction "1_1") (pintype "passive"))
      (node (ref "KMW") (pin "14") (pinfunction "RC6_14") (pintype "bidirectional"))
      (node (ref "R17") (pin "1") (pinfunction "1_1") (pintype "passive"))
    )
    (net (code "15") (name "E2_S") (class "Default")
      (node (ref "C28") (pin "1") (pinfunction "1_1") (pintype "passive"))
      (node (ref "KMW") (pin "12") (pinfunction "RC4_12") (pintype "bidirectional"))
      (node (ref "R15") (pin "2") (pinfunction "2_2") (pintype "passive"))
    )
    (net (code "16") (name "EN_B") (class "Default")
      (node (ref "R46") (pin "1") (pinfunction "1_1") (pintype "passive"))
      (node (ref "U2") (pin "1") (pinfunction "EN_1") (pintype "input"))
    )
    (net (code "17") (name "G") (class "Default")
      (node (ref "KMW") (pin "28") (pinfunction "RA1_28") (pintype "bidirectional"))
      (node (ref "RGB") (pin "2") (pinfunction "GGND_2") (pintype "power_in"))
    )
    (net (code "18") (name "GND") (class "Default")
      (node (ref "C10") (pin "2") (pinfunction "2_2") (pintype "passive"))
      (node (ref "C11") (pin "2") (pinfunction "2_2") (pintype "passive"))
      (node (ref "C12") (pin "2") (pinfunction "2_2") (pintype "passive"))
      (node (ref "C13") (pin "2") (pinfunction "2_2") (pintype "passive"))
      (node (ref "C14") (pin "2") (pinfunction "2_2") (pintype "passive"))
      (node (ref "C15") (pin "2") (pinfunction "2_2") (pintype "passive"))
      (node (ref "C16") (pin "2") (pinfunction "2_2") (pintype "passive"))
      (node (ref "C17") (pin "2") (pinfunction "2_2") (pintype "passive"))
      (node (ref "C18") (pin "2") (pinfunction "2_2") (pintype "passive"))
      (node (ref "C19") (pin "2") (pinfunction "2_2") (pintype "passive"))
      (node (ref "C20") (pin "2") (pinfunction "2_2") (pintype "passive"))
      (node (ref "C21") (pin "2") (pinfunction "2_2") (pintype "passive"))
      (node (ref "C22") (pin "2") (pinfunction "2_2") (pintype "passive"))
      (node (ref "C23") (pin "2") (pinfunction "2_2") (pintype "passive"))
      (node (ref "C24") (pin "2") (pinfunction "2_2") (pintype "passive"))
      (node (ref "C25") (pin "2") (pinfunction "2_2") (pintype "passive"))
      (node (ref "C26") (pin "2") (pinfunction "2_2") (pintype "passive"))
      (node (ref "C27") (pin "2") (pinfunction "2_2") (pintype "passive"))
      (node (ref "C28") (pin "2") (pinfunction "2_2") (pintype "passive"))
      (node (ref "C29") (pin "2") (pinfunction "2_2") (pintype "passive"))
      (node (ref "C30") (pin "2") (pinfunction "2_2") (pintype "passive"))
      (node (ref "C31") (pin "2") (pinfunction "2_2") (pintype "passive"))
      (node (ref "C32") (pin "1") (pinfunction "1_1") (pintype "passive"))
      (node (ref "C33") (pin "1") (pinfunction "1_1") (pintype "passive"))
      (node (ref "C34") (pin "1") (pinfunction "1_1") (pintype "passive"))
      (node (ref "C35") (pin "1") (pinfunction "1_1") (pintype "passive"))
      (node (ref "C36") (pin "2") (pinfunction "2_2") (pintype "passive"))
      (node (ref "C37") (pin "2") (pinfunction "2_2") (pintype "passive"))
      (node (ref "C38") (pin "2") (pinfunction "2_2") (pintype "passive"))
      (node (ref "C39") (pin "2") (pinfunction "2_2") (pintype "passive"))
      (node (ref "C40") (pin "2") (pinfunction "2_2") (pintype "passive"))
      (node (ref "C41") (pin "1") (pinfunction "1_1") (pintype "passive"))
      (node (ref "C42") (pin "1") (pinfunction "1_1") (pintype "passive"))
      (node (ref "C43") (pin "2") (pinfunction "2_2") (pintype "passive"))
      (node (ref "C44") (pin "2") (pinfunction "2_2") (pintype "passive"))
      (node (ref "C45") (pin "1") (pinfunction "1_1") (pintype "passive"))
      (node (ref "C46") (pin "1") (pinfunction "1_1") (pintype "passive"))
      (node (ref "C47") (pin "1") (pinfunction "1_1") (pintype "passive"))
      (node (ref "C48") (pin "2") (pinfunction "2_2") (pintype "passive"))
      (node (ref "C49") (pin "2") (pinfunction "2_2") (pintype "passive"))
      (node (ref "C50") (pin "2") (pinfunction "2_2") (pintype "passive"))
      (node (ref "C51") (pin "2") (pinfunction "2_2") (pintype "passive"))
      (node (ref "C52") (pin "2") (pinfunction "2_2") (pintype "passive"))
      (node (ref "C53") (pin "2") (pinfunction "2_2") (pintype "passive"))
      (node (ref "C54") (pin "2") (pinfunction "2_2") (pintype "passive"))
      (node (ref "C55") (pin "2") (pinfunction "2_2") (pintype "passive"))
      (node (ref "C56") (pin "2") (pinfunction "2_2") (pintype "passive"))
      (node (ref "C57") (pin "2") (pinfunction "2_2") (pintype "passive"))
      (node (ref "C58") (pin "2") (pinfunction "2_2") (pintype "passive"))
      (node (ref "C59") (pin "2") (pinfunction "2_2") (pintype "passive"))
      (node (ref "C60") (pin "2") (pinfunction "2_2") (pintype "passive"))
      (node (ref "E1") (pin "C") (pinfunction "C_C") (pintype "passive"))
      (node (ref "E1") (pin "E") (pinfunction "2_E") (pintype "passive"))
      (node (ref "E2") (pin "C") (pinfunction "C_C") (pintype "passive"))
      (node (ref "E2") (pin "E") (pinfunction "2_E") (pintype "passive"))
      (node (ref "I2C") (pin "2") (pinfunction "2_2") (pintype "passive"))
      (node (ref "ICSP") (pin "3") (pinfunction "3_3") (pintype "passive"))
      (node (ref "JTAG") (pin "1") (pinfunction "1_1") (pintype "passive"))
      (node (ref "JTAG") (pin "11") (pinfunction "11_11") (pintype "passive"))
      (node (ref "JTAG") (pin "13") (pinfunction "13_13") (pintype "passive"))
      (node (ref "JTAG") (pin "3") (pinfunction "3_3") (pintype "passive"))
      (node (ref "JTAG") (pin "5") (pinfunction "5_5") (pintype "passive"))
      (node (ref "JTAG") (pin "7") (pinfunction "7_7") (pintype "passive"))
      (node (ref "JTAG") (pin "9") (pinfunction "9_9") (pintype "passive"))
      (node (ref "KME") (pin "16") (pinfunction "VSS_16") (pintype "power_in"))
      (node (ref "KME") (pin "5") (pinfunction "VSS_5") (pintype "power_in"))
      (node (ref "KME") (pin "EP") (pinfunction "EPAD_EP") (pintype "passive"))
      (node (ref "KMW") (pin "16") (pinfunction "VSS_16") (pintype "power_in"))
      (node (ref "KMW") (pin "5") (pinfunction "VSS_5") (pintype "power_in"))
      (node (ref "KMW") (pin "EP") (pinfunction "EPAD_EP") (pintype "passive"))
      (node (ref "P1") (pin "1") (pinfunction "1_1") (pintype "passive"))
      (node (ref "P10") (pin "4") (pinfunction "4_4") (pintype "passive"))
      (node (ref "P11") (pin "4") (pinfunction "4_4") (pintype "passive"))
      (node (ref "P12") (pin "4") (pinfunction "4_4") (pintype "passive"))
      (node (ref "P13") (pin "1") (pinfunction "1_1") (pintype "passive"))
      (node (ref "P2") (pin "1") (pinfunction "1_1") (pintype "passive"))
      (node (ref "P3") (pin "1") (pinfunction "1_1") (pintype "passive"))
      (node (ref "P4") (pin "3") (pinfunction "3_3") (pintype "passive"))
      (node (ref "P5") (pin "3") (pinfunction "3_3") (pintype "passive"))
      (node (ref "P6") (pin "3") (pinfunction "3_3") (pintype "passive"))
      (node (ref "P7") (pin "4") (pinfunction "4_4") (pintype "passive"))
      (node (ref "P8") (pin "4") (pinfunction "4_4") (pintype "passive"))
      (node (ref "P9") (pin "4") (pinfunction "4_4") (pintype "passive"))
      (node (ref "PWR") (pin "2") (pinfunction "2_2") (pintype "passive"))
      (node (ref "Q1") (pin "2") (pinfunction "S_2") (pintype "passive"))
      (node (ref "R47") (pin "1") (pinfunction "1_1") (pintype "passive"))
      (node (ref "R51") (pin "1") (pinfunction "1_1") (pintype "passive"))
      (node (ref "RESET") (pin "1") (pinfunction "1_1") (pintype "passive"))
      (node (ref "S1") (pin "2") (pinfunction "P_2") (pintype "passive"))
      (node (ref "S2") (pin "2") (pinfunction "P_2") (pintype "passive"))
      (node (ref "TFT") (pin "11") (pinfunction "VSYNC_11") (pintype "bidirectional"))
      (node (ref "TFT") (pin "12") (pinfunction "HSYNC_12") (pintype "bidirectional"))
      (node (ref "TFT") (pin "13") (pinfunction "DOTCLK_13") (pintype "bidirectional"))
      (node (ref "TFT") (pin "14") (pinfunction "DE_14") (pintype "bidirectional"))
      (node (ref "TFT") (pin "15") (pinfunction "DB17_15") (pintype "bidirectional"))
      (node (ref "TFT") (pin "16") (pinfunction "DB16_16") (pintype "bidirectional"))
      (node (ref "TFT") (pin "43") (pinfunction "GND_43") (pintype "bidirectional"))
      (node (ref "TFT") (pin "48") (pinfunction "GND_48") (pintype "bidirectional"))
      (node (ref "TFT") (pin "49") (pinfunction "GND_49") (pintype "bidirectional"))
      (node (ref "TFT") (pin "50") (pinfunction "GND_50") (pintype "bidirectional"))
      (node (ref "TS1") (pin "2") (pinfunction "P_2") (pintype "passive"))
      (node (ref "TS2") (pin "2") (pinfunction "P_2") (pintype "passive"))
      (node (ref "U1") (pin "13") (pinfunction "VSS_13") (pintype "power_in"))
      (node (ref "U1") (pin "31") (pinfunction "AVSS_31") (pintype "power_in"))
      (node (ref "U1") (pin "36") (pinfunction "VSS_36") (pintype "power_in"))
      (node (ref "U1") (pin "45") (pinfunction "VSS_45") (pintype "power_in"))
      (node (ref "U1") (pin "53") (pinfunction "VSS_53") (pintype "power_in"))
      (node (ref "U1") (pin "63") (pinfunction "VSS_63") (pintype "power_in"))
      (node (ref "U1") (pin "75") (pinfunction "VSS_75") (pintype "power_in"))
      (node (ref "U1") (pin "84") (pinfunction "VSS_84") (pintype "power_in"))
      (node (ref "U1") (pin "92") (pinfunction "VSS_92") (pintype "power_in"))
      (node (ref "U2") (pin "5") (pinfunction "GND_5") (pintype "passive"))
      (node (ref "U2") (pin "6") (pinfunction "GND_6") (pintype "passive"))
      (node (ref "U2") (pin "EP") (pinfunction "GND_EP") (pintype "passive"))
      (node (ref "UART") (pin "2") (pinfunction "2_2") (pintype "passive"))
      (node (ref "USB") (pin "5") (pinfunction "GND_5") (pintype "passive"))
      (node (ref "USB") (pin "Z1") (pinfunction "S1_Z1") (pintype "passive"))
      (node (ref "USB") (pin "Z2") (pinfunction "S2_Z2") (pintype "passive"))
      (node (ref "USB") (pin "Z3") (pinfunction "S2_Z3") (pintype "passive"))
      (node (ref "USB") (pin "Z4") (pinfunction "S1_Z4") (pintype "passive"))
      (node (ref "USB") (pin "Z5") (pinfunction "S3_Z5") (pintype "passive"))
      (node (ref "USB") (pin "Z6") (pinfunction "S3_Z6") (pintype "passive"))
      (node (ref "X1") (pin "2") (pinfunction "GND_2") (pintype "power_in"))
      (node (ref "X1") (pin "4") (pinfunction "GND_4") (pintype "power_in"))
    )
    (net (code "19") (name "KME_PCLK") (class "Default")
      (node (ref "KME") (pin "24") (pinfunction "RB6/ICSPCLK_24") (pintype "bidirectional"))
      (node (ref "U1") (pin "59") (pinfunction "SCL2_59") (pintype "bidirectional"))
    )
    (net (code "20") (name "KME_PDAT") (class "Default")
      (node (ref "KME") (pin "25") (pinfunction "RB7/ICSPDAT_25") (pintype "bidirectional"))
      (node (ref "U1") (pin "60") (pinfunction "SDA2_60") (pintype "bidirectional"))
    )
    (net (code "21") (name "KME_~{MCLR}") (class "Default")
      (node (ref "KME") (pin "26") (pinfunction "RE3/~{MCLR}/VPP_26") (pintype "bidirectional"))
      (node (ref "U1") (pin "73") (pinfunction "SOSCO_73") (pintype "bidirectional"))
    )
    (net (code "22") (name "KMW_PCLK") (class "Default")
      (node (ref "KMW") (pin "24") (pinfunction "RB6/ICSPCLK_24") (pintype "bidirectional"))
      (node (ref "U1") (pin "58") (pinfunction "SCL3_58") (pintype "bidirectional"))
    )
    (net (code "23") (name "KMW_PDAT") (class "Default")
      (node (ref "KMW") (pin "25") (pinfunction "RB7/ICSPDAT_25") (pintype "bidirectional"))
      (node (ref "U1") (pin "57") (pinfunction "SDA3_57") (pintype "bidirectional"))
    )
    (net (code "24") (name "KMW_~{MCLR}") (class "Default")
      (node (ref "KMW") (pin "26") (pinfunction "RE3/~{MCLR}/VPP_26") (pintype "bidirectional"))
      (node (ref "U1") (pin "72") (pinfunction "SOSCI_72") (pintype "bidirectional"))
    )
    (net (code "25") (name "LED_A1") (class "Default")
      (node (ref "R41") (pin "2") (pinfunction "2_2") (pintype "passive"))
      (node (ref "TFT") (pin "2") (pinfunction "LEDA_2") (pintype "bidirectional"))
    )
    (net (code "26") (name "LED_A2") (class "Default")
      (node (ref "R42") (pin "2") (pinfunction "2_2") (pintype "passive"))
      (node (ref "TFT") (pin "3") (pinfunction "LEDA_3") (pintype "bidirectional"))
    )
    (net (code "27") (name "LED_A3") (class "Default")
      (node (ref "R43") (pin "2") (pinfunction "2_2") (pintype "passive"))
      (node (ref "TFT") (pin "4") (pinfunction "LEDA_4") (pintype "bidirectional"))
    )
    (net (code "28") (name "LED_A4") (class "Default")
      (node (ref "R44") (pin "2") (pinfunction "2_2") (pintype "passive"))
      (node (ref "TFT") (pin "5") (pinfunction "LEDA_5") (pintype "bidirectional"))
    )
    (net (code "29") (name "LED_CK") (class "Default")
      (node (ref "Q1") (pin "3") (pinfunction "D_3") (pintype "passive"))
      (node (ref "TFT") (pin "1") (pinfunction "LEDK_1") (pintype "bidirectional"))
    )
    (net (code "30") (name "Net-(E1-PadA)") (class "Default")
      (node (ref "E1") (pin "A") (pinfunction "A_A") (pintype "passive"))
      (node (ref "R26") (pin "2") (pinfunction "2_2") (pintype "passive"))
    )
    (net (code "31") (name "Net-(E1-PadB)") (class "Default")
      (node (ref "E1") (pin "B") (pinfunction "B_B") (pintype "passive"))
      (node (ref "R27") (pin "2") (pinfunction "2_2") (pintype "passive"))
    )
    (net (code "32") (name "Net-(E1D-1)") (class "Default")
      (node (ref "E1") (pin "D") (pinfunction "1_D") (pintype "passive"))
      (node (ref "R24") (pin "1") (pinfunction "1_1") (pintype "passive"))
    )
    (net (code "33") (name "Net-(E2-PadA)") (class "Default")
      (node (ref "E2") (pin "A") (pinfunction "A_A") (pintype "passive"))
      (node (ref "R16") (pin "2") (pinfunction "2_2") (pintype "passive"))
    )
    (net (code "34") (name "Net-(E2-PadB)") (class "Default")
      (node (ref "E2") (pin "B") (pinfunction "B_B") (pintype "passive"))
      (node (ref "R17") (pin "2") (pinfunction "2_2") (pintype "passive"))
    )
    (net (code "35") (name "Net-(E2D-1)") (class "Default")
      (node (ref "E2") (pin "D") (pinfunction "1_D") (pintype "passive"))
      (node (ref "R15") (pin "1") (pinfunction "1_1") (pintype "passive"))
    )
    (net (code "36") (name "Net-(KME-RA2)") (class "Default")
      (node (ref "KME") (pin "1") (pinfunction "RA2_1") (pintype "bidirectional"))
      (node (ref "TP1") (pin "TP") (pinfunction "TP_TP") (pintype "input"))
    )
    (net (code "37") (name "Net-(KME-RA5)") (class "Default")
      (node (ref "KME") (pin "4") (pinfunction "RA5_4") (pintype "bidirectional"))
      (node (ref "TP2") (pin "TP") (pinfunction "TP_TP") (pintype "input"))
    )
    (net (code "38") (name "Net-(KME-RA6)") (class "Default")
      (node (ref "KME") (pin "7") (pinfunction "RA6_7") (pintype "bidirectional"))
      (node (ref "TP3") (pin "TP") (pinfunction "TP_TP") (pintype "input"))
    )
    (net (code "39") (name "Net-(KMW-RC0)") (class "Default")
      (node (ref "KMW") (pin "8") (pinfunction "RC0_8") (pintype "bidirectional"))
      (node (ref "TP5") (pin "TP") (pinfunction "TP_TP") (pintype "input"))
    )
    (net (code "40") (name "Net-(KMW-RC7)") (class "Default")
      (node (ref "KMW") (pin "15") (pinfunction "RC7_15") (pintype "bidirectional"))
      (node (ref "TP4") (pin "TP") (pinfunction "TP_TP") (pintype "input"))
    )
    (net (code "41") (name "Net-(P1-Pad4)") (class "Default")
      (node (ref "P1") (pin "4") (pinfunction "4_4") (pintype "passive"))
      (node (ref "R10") (pin "2") (pinfunction "2_2") (pintype "passive"))
    )
    (net (code "42") (name "Net-(P2-Pad4)") (class "Default")
      (node (ref "P2") (pin "4") (pinfunction "4_4") (pintype "passive"))
      (node (ref "R11") (pin "2") (pinfunction "2_2") (pintype "passive"))
    )
    (net (code "43") (name "Net-(P3-Pad4)") (class "Default")
      (node (ref "P3") (pin "4") (pinfunction "4_4") (pintype "passive"))
      (node (ref "R12") (pin "2") (pinfunction "2_2") (pintype "passive"))
    )
    (net (code "44") (name "Net-(P4-Pad2)") (class "Default")
      (node (ref "P4") (pin "2") (pinfunction "2_2") (pintype "passive"))
      (node (ref "R34") (pin "1") (pinfunction "1_1") (pintype "passive"))
    )
    (net (code "45") (name "Net-(P5-Pad2)") (class "Default")
      (node (ref "P5") (pin "2") (pinfunction "2_2") (pintype "passive"))
      (node (ref "R35") (pin "1") (pinfunction "1_1") (pintype "passive"))
    )
    (net (code "46") (name "Net-(P6-Pad2)") (class "Default")
      (node (ref "P6") (pin "2") (pinfunction "2_2") (pintype "passive"))
      (node (ref "R36") (pin "1") (pinfunction "1_1") (pintype "passive"))
    )
    (net (code "47") (name "Net-(P7-Pad1)") (class "Default")
      (node (ref "P7") (pin "1") (pinfunction "1_1") (pintype "passive"))
      (node (ref "R21") (pin "2") (pinfunction "2_2") (pintype "passive"))
    )
    (net (code "48") (name "Net-(P8-Pad1)") (class "Default")
      (node (ref "P8") (pin "1") (pinfunction "1_1") (pintype "passive"))
      (node (ref "R28") (pin "2") (pinfunction "2_2") (pintype "passive"))
    )
    (net (code "49") (name "Net-(P9-Pad1)") (class "Default")
      (node (ref "P9") (pin "1") (pinfunction "1_1") (pintype "passive"))
      (node (ref "R30") (pin "2") (pinfunction "2_2") (pintype "passive"))
    )
    (net (code "50") (name "Net-(P10-Pad1)") (class "Default")
      (node (ref "P10") (pin "1") (pinfunction "1_1") (pintype "passive"))
      (node (ref "R22") (pin "2") (pinfunction "2_2") (pintype "passive"))
    )
    (net (code "51") (name "Net-(P11-Pad1)") (class "Default")
      (node (ref "P11") (pin "1") (pinfunction "1_1") (pintype "passive"))
      (node (ref "R29") (pin "2") (pinfunction "2_2") (pintype "passive"))
    )
    (net (code "52") (name "Net-(P12-Pad1)") (class "Default")
      (node (ref "P12") (pin "1") (pinfunction "1_1") (pintype "passive"))
      (node (ref "R31") (pin "2") (pinfunction "2_2") (pintype "passive"))
    )
    (net (code "53") (name "Net-(P13-Pad4)") (class "Default")
      (node (ref "P13") (pin "4") (pinfunction "4_4") (pintype "passive"))
      (node (ref "R18") (pin "1") (pinfunction "1_1") (pintype "passive"))
    )
    (net (code "54") (name "Net-(Q1-G)") (class "Default")
      (node (ref "Q1") (pin "1") (pinfunction "G_1") (pintype "passive"))
      (node (ref "R40") (pin "1") (pinfunction "1_1") (pintype "passive"))
    )
    (net (code "55") (name "Net-(R48-Pad1)") (class "Default")
      (node (ref "R48") (pin "1") (pinfunction "1_1") (pintype "passive"))
      (node (ref "RESET") (pin "4") (pinfunction "4_4") (pintype "passive"))
    )
    (net (code "56") (name "Net-(RGB-BLUE)") (class "Default")
      (node (ref "R37") (pin "2") (pinfunction "2_2") (pintype "passive"))
      (node (ref "RGB") (pin "6") (pinfunction "BLUE_6") (pintype "bidirectional"))
    )
    (net (code "57") (name "Net-(RGB-GRN)") (class "Default")
      (node (ref "R38") (pin "2") (pinfunction "2_2") (pintype "passive"))
      (node (ref "RGB") (pin "5") (pinfunction "GRN_5") (pintype "bidirectional"))
    )
    (net (code "58") (name "Net-(RGB-RED)") (class "Default")
      (node (ref "R39") (pin "2") (pinfunction "2_2") (pintype "passive"))
      (node (ref "RGB") (pin "4") (pinfunction "RED_4") (pintype "bidirectional"))
    )
    (net (code "59") (name "Net-(S1-O)") (class "Default")
      (node (ref "R32") (pin "2") (pinfunction "2_2") (pintype "passive"))
      (node (ref "S1") (pin "1") (pinfunction "O_1") (pintype "passive"))
    )
    (net (code "60") (name "Net-(S1-S)") (class "Default")
      (node (ref "R33") (pin "2") (pinfunction "2_2") (pintype "passive"))
      (node (ref "S1") (pin "3") (pinfunction "S_3") (pintype "passive"))
    )
    (net (code "61") (name "Net-(S2-O)") (class "Default")
      (node (ref "R13") (pin "2") (pinfunction "2_2") (pintype "passive"))
      (node (ref "S2") (pin "1") (pinfunction "O_1") (pintype "passive"))
    )
    (net (code "62") (name "Net-(S2-S)") (class "Default")
      (node (ref "R14") (pin "2") (pinfunction "2_2") (pintype "passive"))
      (node (ref "S2") (pin "3") (pinfunction "S_3") (pintype "passive"))
    )
    (net (code "63") (name "Net-(TS1-O)") (class "Default")
      (node (ref "R23") (pin "2") (pinfunction "2_2") (pintype "passive"))
      (node (ref "TS1") (pin "1") (pinfunction "O_1") (pintype "passive"))
    )
    (net (code "64") (name "Net-(TS1-S)") (class "Default")
      (node (ref "R25") (pin "2") (pinfunction "2_2") (pintype "passive"))
      (node (ref "TS1") (pin "3") (pinfunction "S_3") (pintype "passive"))
    )
    (net (code "65") (name "Net-(TS2-O)") (class "Default")
      (node (ref "R19") (pin "2") (pinfunction "2_2") (pintype "passive"))
      (node (ref "TS2") (pin "1") (pinfunction "O_1") (pintype "passive"))
    )
    (net (code "66") (name "Net-(TS2-S)") (class "Default")
      (node (ref "R20") (pin "2") (pinfunction "2_2") (pintype "passive"))
      (node (ref "TS2") (pin "3") (pinfunction "S_3") (pintype "passive"))
    )
    (net (code "67") (name "Net-(U2-FB)") (class "Default")
      (node (ref "R45") (pin "1") (pinfunction "1_1") (pintype "passive"))
      (node (ref "R47") (pin "2") (pinfunction "2_2") (pintype "passive"))
      (node (ref "U2") (pin "7") (pinfunction "FB_7") (pintype "output"))
    )
    (net (code "68") (name "OSC1") (class "Default")
      (node (ref "C20") (pin "1") (pinfunction "1_1") (pintype "passive"))
      (node (ref "U1") (pin "49") (pinfunction "OSC1_49") (pintype "bidirectional"))
      (node (ref "X1") (pin "3") (pinfunction "2_3") (pintype "passive"))
    )
    (net (code "69") (name "OSC2") (class "Default")
      (node (ref "C19") (pin "1") (pinfunction "1_1") (pintype "passive"))
      (node (ref "U1") (pin "50") (pinfunction "OSC2_50") (pintype "bidirectional"))
      (node (ref "X1") (pin "1") (pinfunction "1_1") (pintype "passive"))
    )
    (net (code "70") (name "P1") (class "Default")
      (node (ref "C21") (pin "1") (pinfunction "1_1") (pintype "passive"))
      (node (ref "KME") (pin "21") (pinfunction "RB3_21") (pintype "bidirectional"))
      (node (ref "R10") (pin "1") (pinfunction "1_1") (pintype "passive"))
    )
    (net (code "71") (name "P2") (class "Default")
      (node (ref "C22") (pin "1") (pinfunction "1_1") (pintype "passive"))
      (node (ref "KME") (pin "22") (pinfunction "RB4_22") (pintype "bidirectional"))
      (node (ref "R11") (pin "1") (pinfunction "1_1") (pintype "passive"))
    )
    (net (code "72") (name "P3") (class "Default")
      (node (ref "C23") (pin "1") (pinfunction "1_1") (pintype "passive"))
      (node (ref "KME") (pin "23") (pinfunction "RB5_23") (pintype "bidirectional"))
      (node (ref "R12") (pin "1") (pinfunction "1_1") (pintype "passive"))
    )
    (net (code "73") (name "P4") (class "Default")
      (node (ref "C45") (pin "2") (pinfunction "2_2") (pintype "passive"))
      (node (ref "KME") (pin "15") (pinfunction "RC7_15") (pintype "bidirectional"))
      (node (ref "R34") (pin "2") (pinfunction "2_2") (pintype "passive"))
    )
    (net (code "74") (name "P5") (class "Default")
      (node (ref "C46") (pin "2") (pinfunction "2_2") (pintype "passive"))
      (node (ref "KME") (pin "14") (pinfunction "RC6_14") (pintype "bidirectional"))
      (node (ref "R35") (pin "2") (pinfunction "2_2") (pintype "passive"))
    )
    (net (code "75") (name "P6") (class "Default")
      (node (ref "C47") (pin "2") (pinfunction "2_2") (pintype "passive"))
      (node (ref "KME") (pin "13") (pinfunction "RC5_13") (pintype "bidirectional"))
      (node (ref "R36") (pin "2") (pinfunction "2_2") (pintype "passive"))
    )
    (net (code "76") (name "P7") (class "Default")
      (node (ref "C32") (pin "2") (pinfunction "2_2") (pintype "passive"))
      (node (ref "KME") (pin "12") (pinfunction "RC4_12") (pintype "bidirectional"))
      (node (ref "R21") (pin "1") (pinfunction "1_1") (pintype "passive"))
    )
    (net (code "77") (name "P8") (class "Default")
      (node (ref "C34") (pin "2") (pinfunction "2_2") (pintype "passive"))
      (node (ref "KME") (pin "11") (pinfunction "RC3_11") (pintype "bidirectional"))
      (node (ref "R28") (pin "1") (pinfunction "1_1") (pintype "passive"))
    )
    (net (code "78") (name "P9") (class "Default")
      (node (ref "C41") (pin "2") (pinfunction "2_2") (pintype "passive"))
      (node (ref "KME") (pin "10") (pinfunction "RC2_10") (pintype "bidirectional"))
      (node (ref "R30") (pin "1") (pinfunction "1_1") (pintype "passive"))
    )
    (net (code "79") (name "P10") (class "Default")
      (node (ref "C33") (pin "2") (pinfunction "2_2") (pintype "passive"))
      (node (ref "KME") (pin "20") (pinfunction "RB2_20") (pintype "bidirectional"))
      (node (ref "R22") (pin "1") (pinfunction "1_1") (pintype "passive"))
    )
    (net (code "80") (name "P11") (class "Default")
      (node (ref "C35") (pin "2") (pinfunction "2_2") (pintype "passive"))
      (node (ref "KME") (pin "19") (pinfunction "RB1_19") (pintype "bidirectional"))
      (node (ref "R29") (pin "1") (pinfunction "1_1") (pintype "passive"))
    )
    (net (code "81") (name "P12") (class "Default")
      (node (ref "C42") (pin "2") (pinfunction "2_2") (pintype "passive"))
      (node (ref "KME") (pin "18") (pinfunction "RB0_18") (pintype "bidirectional"))
      (node (ref "R31") (pin "1") (pinfunction "1_1") (pintype "passive"))
    )
    (net (code "82") (name "P13") (class "Default")
      (node (ref "C29") (pin "1") (pinfunction "1_1") (pintype "passive"))
      (node (ref "KMW") (pin "23") (pinfunction "RB5_23") (pintype "bidirectional"))
      (node (ref "R18") (pin "2") (pinfunction "2_2") (pintype "passive"))
    )
    (net (code "83") (name "PGEC1") (class "Default")
      (node (ref "ICSP") (pin "5") (pinfunction "5_5") (pintype "passive"))
      (node (ref "U1") (pin "24") (pinfunction "RB1_24") (pintype "bidirectional"))
    )
    (net (code "84") (name "PGED1") (class "Default")
      (node (ref "ICSP") (pin "4") (pinfunction "4_4") (pintype "passive"))
      (node (ref "U1") (pin "25") (pinfunction "RB0_25") (pintype "bidirectional"))
    )
    (net (code "85") (name "PMD0") (class "Default")
      (node (ref "TFT") (pin "32") (pinfunction "DB0_32") (pintype "bidirectional"))
      (node (ref "U1") (pin "91") (pinfunction "PMD0_91") (pintype "bidirectional"))
    )
    (net (code "86") (name "PMD1") (class "Default")
      (node (ref "TFT") (pin "31") (pinfunction "DB1_31") (pintype "bidirectional"))
      (node (ref "U1") (pin "94") (pinfunction "PMD1_94") (pintype "bidirectional"))
    )
    (net (code "87") (name "PMD2") (class "Default")
      (node (ref "TFT") (pin "30") (pinfunction "DB2_30") (pintype "bidirectional"))
      (node (ref "U1") (pin "98") (pinfunction "PMD2_98") (pintype "bidirectional"))
    )
    (net (code "88") (name "PMD3") (class "Default")
      (node (ref "TFT") (pin "29") (pinfunction "DB3_29") (pintype "bidirectional"))
      (node (ref "U1") (pin "99") (pinfunction "PMD3_99") (pintype "bidirectional"))
    )
    (net (code "89") (name "PMD4") (class "Default")
      (node (ref "TFT") (pin "28") (pinfunction "DB4_28") (pintype "bidirectional"))
      (node (ref "U1") (pin "100") (pinfunction "PMD4_100") (pintype "bidirectional"))
    )
    (net (code "90") (name "PMD5") (class "Default")
      (node (ref "TFT") (pin "27") (pinfunction "DB5_27") (pintype "bidirectional"))
      (node (ref "U1") (pin "3") (pinfunction "PMD5_3") (pintype "bidirectional"))
    )
    (net (code "91") (name "PMD6") (class "Default")
      (node (ref "TFT") (pin "26") (pinfunction "DB6_26") (pintype "bidirectional"))
      (node (ref "U1") (pin "4") (pinfunction "PMD6_4") (pintype "bidirectional"))
    )
    (net (code "92") (name "PMD7") (class "Default")
      (node (ref "TFT") (pin "25") (pinfunction "DB7_25") (pintype "bidirectional"))
      (node (ref "U1") (pin "5") (pinfunction "PMD7_5") (pintype "bidirectional"))
    )
    (net (code "93") (name "PMD8") (class "Default")
      (node (ref "TFT") (pin "24") (pinfunction "DB8_24") (pintype "bidirectional"))
      (node (ref "U1") (pin "88") (pinfunction "PMD8_88") (pintype "bidirectional"))
    )
    (net (code "94") (name "PMD9") (class "Default")
      (node (ref "TFT") (pin "23") (pinfunction "DB9_23") (pintype "bidirectional"))
      (node (ref "U1") (pin "87") (pinfunction "PMD9_87") (pintype "bidirectional"))
    )
    (net (code "95") (name "PMD10") (class "Default")
      (node (ref "TFT") (pin "22") (pinfunction "DB10_22") (pintype "bidirectional"))
      (node (ref "U1") (pin "86") (pinfunction "PMD10_86") (pintype "bidirectional"))
    )
    (net (code "96") (name "PMD11") (class "Default")
      (node (ref "TFT") (pin "21") (pinfunction "DB11_21") (pintype "bidirectional"))
      (node (ref "U1") (pin "85") (pinfunction "PMD11_85") (pintype "bidirectional"))
    )
    (net (code "97") (name "PMD12") (class "Default")
      (node (ref "TFT") (pin "20") (pinfunction "DB12_20") (pintype "bidirectional"))
      (node (ref "U1") (pin "79") (pinfunction "PMD12_79") (pintype "bidirectional"))
    )
    (net (code "98") (name "PMD13") (class "Default")
      (node (ref "TFT") (pin "19") (pinfunction "DB13_19") (pintype "bidirectional"))
      (node (ref "U1") (pin "80") (pinfunction "PMD13_80") (pintype "bidirectional"))
    )
    (net (code "99") (name "PMD14") (class "Default")
      (node (ref "TFT") (pin "18") (pinfunction "DB14_18") (pintype "bidirectional"))
      (node (ref "U1") (pin "77") (pinfunction "PMD14_77") (pintype "bidirectional"))
    )
    (net (code "100") (name "PMD15") (class "Default")
      (node (ref "TFT") (pin "17") (pinfunction "DB15_17") (pintype "bidirectional"))
      (node (ref "U1") (pin "78") (pinfunction "PMD15_78") (pintype "bidirectional"))
    )
    (net (code "101") (name "PMRD") (class "Default")
      (node (ref "TFT") (pin "35") (pinfunction "/RD_35") (pintype "bidirectional"))
      (node (ref "U1") (pin "9") (pinfunction "PMRD_9") (pintype "bidirectional"))
    )
    (net (code "102") (name "PMWR") (class "Default")
      (node (ref "TFT") (pin "36") (pinfunction "/WR_RS_36") (pintype "bidirectional"))
      (node (ref "U1") (pin "8") (pinfunction "PMWR_8") (pintype "bidirectional"))
    )
    (net (code "103") (name "R") (class "Default")
      (node (ref "KMW") (pin "1") (pinfunction "RA2_1") (pintype "bidirectional"))
      (node (ref "RGB") (pin "3") (pinfunction "RGND_3") (pintype "power_in"))
    )
    (net (code "104") (name "RA4") (class "Default")
      (node (ref "U1") (pin "61") (pinfunction "PMA14_61") (pintype "bidirectional"))
    )
    (net (code "105") (name "RA5") (class "Default")
      (node (ref "TFT") (pin "47") (pinfunction "TP_RES_47") (pintype "bidirectional"))
      (node (ref "U1") (pin "2") (pinfunction "PMA5_2") (pintype "bidirectional"))
    )
    (net (code "106") (name "RA6") (class "Default")
      (node (ref "U1") (pin "89") (pinfunction "SQICLK_89") (pintype "bidirectional"))
    )
    (net (code "107") (name "RA7") (class "Default")
      (node (ref "U1") (pin "90") (pinfunction "SQID3_90") (pintype "bidirectional"))
    )
    (net (code "108") (name "RA9") (class "Default")
      (node (ref "U1") (pin "28") (pinfunction "RA9_28") (pintype "bidirectional"))
    )
    (net (code "109") (name "RA10") (class "Default")
      (node (ref "U1") (pin "29") (pinfunction "RA10_29") (pintype "bidirectional"))
    )
    (net (code "110") (name "RB4") (class "Default")
      (node (ref "U1") (pin "21") (pinfunction "RB4_21") (pintype "bidirectional"))
    )
    (net (code "111") (name "RB12") (class "Default")
      (node (ref "TFT") (pin "9") (pinfunction "IM3_9") (pintype "bidirectional"))
      (node (ref "U1") (pin "41") (pinfunction "PMA11_41") (pintype "bidirectional"))
    )
    (net (code "112") (name "RB13") (class "Default")
      (node (ref "TFT") (pin "8") (pinfunction "IM2_8") (pintype "bidirectional"))
      (node (ref "U1") (pin "42") (pinfunction "RB13_42") (pintype "bidirectional"))
    )
    (net (code "113") (name "RD1") (class "Default")
      (node (ref "U1") (pin "76") (pinfunction "SCK1_76") (pintype "bidirectional"))
    )
    (net (code "114") (name "RG12") (class "Default")
      (node (ref "U1") (pin "96") (pinfunction "SQID1_96") (pintype "bidirectional"))
    )
    (net (code "115") (name "RG13") (class "Default")
      (node (ref "U1") (pin "97") (pinfunction "SQID0_97") (pintype "bidirectional"))
    )
    (net (code "116") (name "RG14") (class "Default")
      (node (ref "U1") (pin "95") (pinfunction "SQID2_95") (pintype "bidirectional"))
    )
    (net (code "117") (name "RG15") (class "Default")
      (node (ref "TFT") (pin "39") (pinfunction "TE_39") (pintype "bidirectional"))
      (node (ref "U1") (pin "1") (pinfunction "RG15_1") (pintype "bidirectional"))
    )
    (net (code "118") (name "RPB2{slash}4RX{slash}6RX{slash}SS2{slash}SDI6") (class "Default")
      (node (ref "U1") (pin "23") (pinfunction "RB2_23") (pintype "bidirectional"))
    )
    (net (code "119") (name "RPB3{slash}3RX{slash}SDI2{slash}SDI4") (class "Default")
      (node (ref "U1") (pin "22") (pinfunction "RB3_22") (pintype "bidirectional"))
    )
    (net (code "120") (name "RPB5") (class "Default")
      (node (ref "ICSP") (pin "6") (pinfunction "6_6") (pintype "passive"))
      (node (ref "U1") (pin "20") (pinfunction "RB5_20") (pintype "bidirectional"))
    )
    (net (code "121") (name "RPB6{slash}4RX{slash}6RX{slash}SS2{slash}SDI6") (class "Default")
      (node (ref "U1") (pin "26") (pinfunction "RB6_26") (pintype "bidirectional"))
    )
    (net (code "122") (name "RPB7{slash}2RX{slash}SS1{slash}SS3-SS5") (class "Default")
      (node (ref "U1") (pin "27") (pinfunction "RB7_27") (pintype "bidirectional"))
    )
    (net (code "123") (name "RPB8{slash}2RX{slash}SS1{slash}SS3-SS5") (class "Default")
      (node (ref "U1") (pin "32") (pinfunction "PMA10_32") (pintype "bidirectional"))
    )
    (net (code "124") (name "RPB9{slash}1RX{slash}5RX{slash}SDI1{slash}SDI3{slash}SDI5{slash}SS6") (class "Default")
      (node (ref "U1") (pin "33") (pinfunction "PMA7_33") (pintype "bidirectional"))
    )
    (net (code "125") (name "RPB10{slash}1RX{slash}5RX{slash}SDI1{slash}SDI3{slash}SDI5{slash}SS6") (class "Default")
      (node (ref "U1") (pin "34") (pinfunction "PMA13_34") (pintype "bidirectional"))
    )
    (net (code "126") (name "RPB14") (class "Default")
      (node (ref "TFT") (pin "7") (pinfunction "IM1_7") (pintype "bidirectional"))
      (node (ref "U1") (pin "43") (pinfunction "PMA1_43") (pintype "bidirectional"))
    )
    (net (code "127") (name "RPB15") (class "Default")
      (node (ref "TFT") (pin "6") (pinfunction "IM0_6") (pintype "bidirectional"))
      (node (ref "U1") (pin "44") (pinfunction "PMA0_44") (pintype "bidirectional"))
    )
    (net (code "128") (name "RPD0") (class "Default")
      (node (ref "U1") (pin "71") (pinfunction "RTCC_71") (pintype "bidirectional"))
    )
    (net (code "129") (name "RPD4") (class "Default")
      (node (ref "U1") (pin "81") (pinfunction "SQICS0_81") (pintype "bidirectional"))
    )
    (net (code "130") (name "RPD5") (class "Default")
      (node (ref "U1") (pin "82") (pinfunction "SQICS1_82") (pintype "bidirectional"))
    )
    (net (code "131") (name "RPD10") (class "Default")
      (node (ref "R40") (pin "2") (pinfunction "2_2") (pintype "passive"))
      (node (ref "U1") (pin "69") (pinfunction "SCK4_69") (pintype "bidirectional"))
    )
    (net (code "132") (name "RPD11") (class "Default")
      (node (ref "TFT") (pin "10") (pinfunction "/RESET_10") (pintype "bidirectional"))
      (node (ref "U1") (pin "70") (pinfunction "RD11_70") (pintype "bidirectional"))
    )
    (net (code "133") (name "RPD15") (class "Default")
      (node (ref "U1") (pin "47") (pinfunction "RD14_47") (pintype "bidirectional"))
    )
    (net (code "134") (name "RPE8") (class "Default")
      (node (ref "U1") (pin "18") (pinfunction "RE8_18") (pintype "bidirectional"))
      (node (ref "UART") (pin "3") (pinfunction "3_3") (pintype "passive"))
    )
    (net (code "135") (name "RPE9") (class "Default")
      (node (ref "U1") (pin "19") (pinfunction "RE9_19") (pintype "bidirectional"))
      (node (ref "UART") (pin "1") (pinfunction "1_1") (pintype "passive"))
    )
    (net (code "136") (name "RPG9") (class "Default")
      (node (ref "TFT") (pin "46") (pinfunction "TP_IRQ_46") (pintype "bidirectional"))
      (node (ref "U1") (pin "16") (pinfunction "PMA2_16") (pintype "bidirectional"))
    )
    (net (code "137") (name "S1_A") (class "Default")
      (node (ref "C44") (pin "1") (pinfunction "1_1") (pintype "passive"))
      (node (ref "KMW") (pin "3") (pinfunction "RA4_3") (pintype "bidirectional"))
      (node (ref "R32") (pin "1") (pinfunction "1_1") (pintype "passive"))
    )
    (net (code "138") (name "S1_B") (class "Default")
      (node (ref "C43") (pin "1") (pinfunction "1_1") (pintype "passive"))
      (node (ref "KMW") (pin "2") (pinfunction "RA3_2") (pintype "bidirectional"))
      (node (ref "R33") (pin "1") (pinfunction "1_1") (pintype "passive"))
    )
    (net (code "139") (name "S2_A") (class "Default")
      (node (ref "C25") (pin "1") (pinfunction "1_1") (pintype "passive"))
      (node (ref "KME") (pin "28") (pinfunction "RA1_28") (pintype "bidirectional"))
      (node (ref "R13") (pin "1") (pinfunction "1_1") (pintype "passive"))
    )
    (net (code "140") (name "S2_B") (class "Default")
      (node (ref "C24") (pin "1") (pinfunction "1_1") (pintype "passive"))
      (node (ref "KME") (pin "27") (pinfunction "RA0_27") (pintype "bidirectional"))
      (node (ref "R14") (pin "1") (pinfunction "1_1") (pintype "passive"))
    )
    (net (code "141") (name "SCK6") (class "Default")
      (node (ref "TFT") (pin "37") (pinfunction "RS_SCL_37") (pintype "bidirectional"))
      (node (ref "U1") (pin "48") (pinfunction "RD15_48") (pintype "bidirectional"))
    )
    (net (code "142") (name "SCL1") (class "Default")
      (node (ref "TFT") (pin "44") (pinfunction "TP_SCK_44") (pintype "bidirectional"))
      (node (ref "U1") (pin "66") (pinfunction "SCL1_66") (pintype "bidirectional"))
    )
    (net (code "143") (name "SCL4") (class "Default")
      (node (ref "I2C") (pin "1") (pinfunction "1_1") (pintype "passive"))
      (node (ref "U1") (pin "12") (pinfunction "PMA3_12") (pintype "bidirectional"))
    )
    (net (code "144") (name "SCL5") (class "Default")
      (node (ref "U1") (pin "65") (pinfunction "PMA8_65") (pintype "bidirectional"))
    )
    (net (code "145") (name "SDA1") (class "Default")
      (node (ref "TFT") (pin "45") (pinfunction "TP_SDA_45") (pintype "bidirectional"))
      (node (ref "U1") (pin "67") (pinfunction "SDA1_67") (pintype "bidirectional"))
    )
    (net (code "146") (name "SDA4") (class "Default")
      (node (ref "I2C") (pin "3") (pinfunction "3_3") (pintype "passive"))
      (node (ref "U1") (pin "11") (pinfunction "PMA4_11") (pintype "bidirectional"))
    )
    (net (code "147") (name "SDA5") (class "Default")
      (node (ref "U1") (pin "64") (pinfunction "PMA9_64") (pintype "bidirectional"))
    )
    (net (code "148") (name "SDI6") (class "Default")
      (node (ref "TFT") (pin "33") (pinfunction "SDO_33") (pintype "bidirectional"))
      (node (ref "U1") (pin "7") (pinfunction "PMA12_7") (pintype "bidirectional"))
    )
    (net (code "149") (name "SDO6") (class "Default")
      (node (ref "TFT") (pin "34") (pinfunction "SDI_34") (pintype "bidirectional"))
      (node (ref "U1") (pin "10") (pinfunction "RG6_10") (pintype "bidirectional"))
    )
    (net (code "150") (name "TCK") (class "Default")
      (node (ref "JTAG") (pin "6") (pinfunction "6_6") (pintype "passive"))
      (node (ref "U1") (pin "38") (pinfunction "TCK_38") (pintype "bidirectional"))
    )
    (net (code "151") (name "TDI") (class "Default")
      (node (ref "JTAG") (pin "10") (pinfunction "10_10") (pintype "passive"))
      (node (ref "U1") (pin "39") (pinfunction "TDI_39") (pintype "bidirectional"))
    )
    (net (code "152") (name "TDO") (class "Default")
      (node (ref "JTAG") (pin "8") (pinfunction "8_8") (pintype "passive"))
      (node (ref "U1") (pin "40") (pinfunction "TDO_40") (pintype "bidirectional"))
    )
    (net (code "153") (name "TMS") (class "Default")
      (node (ref "JTAG") (pin "4") (pinfunction "4_4") (pintype "passive"))
      (node (ref "U1") (pin "17") (pinfunction "TMS_17") (pintype "bidirectional"))
    )
    (net (code "154") (name "TS1_A") (class "Default")
      (node (ref "C37") (pin "1") (pinfunction "1_1") (pintype "passive"))
      (node (ref "KMW") (pin "20") (pinfunction "RB2_20") (pintype "bidirectional"))
      (node (ref "R23") (pin "1") (pinfunction "1_1") (pintype "passive"))
    )
    (net (code "155") (name "TS1_B") (class "Default")
      (node (ref "C36") (pin "1") (pinfunction "1_1") (pintype "passive"))
      (node (ref "KMW") (pin "21") (pinfunction "RB3_21") (pintype "bidirectional"))
      (node (ref "R25") (pin "1") (pinfunction "1_1") (pintype "passive"))
    )
    (net (code "156") (name "TS2_A") (class "Default")
      (node (ref "C31") (pin "1") (pinfunction "1_1") (pintype "passive"))
      (node (ref "KMW") (pin "10") (pinfunction "RC2_10") (pintype "bidirectional"))
      (node (ref "R19") (pin "1") (pinfunction "1_1") (pintype "passive"))
    )
    (net (code "157") (name "TS2_B") (class "Default")
      (node (ref "C30") (pin "1") (pinfunction "1_1") (pintype "passive"))
      (node (ref "KMW") (pin "11") (pinfunction "RC3_11") (pintype "bidirectional"))
      (node (ref "R20") (pin "1") (pinfunction "1_1") (pintype "passive"))
    )
    (net (code "158") (name "USBID") (class "Default")
      (node (ref "U1") (pin "56") (pinfunction "USBID_56") (pintype "bidirectional"))
      (node (ref "USB") (pin "4") (pinfunction "ID_4") (pintype "passive"))
    )
    (net (code "159") (name "VBUS") (class "Default")
      (node (ref "D10") (pin "A") (pinfunction "A_A") (pintype "passive"))
      (node (ref "U1") (pin "51") (pinfunction "VBUS_51") (pintype "power_in"))
      (node (ref "USB") (pin "1") (pinfunction "VBUS_1") (pintype "passive"))
    )
    (net (code "160") (name "VOUT_B") (class "Default")
      (node (ref "C53") (pin "1") (pinfunction "1_1") (pintype "passive"))
      (node (ref "FB2") (pin "1") (pinfunction "1_1") (pintype "passive"))
      (node (ref "R45") (pin "2") (pinfunction "2_2") (pintype "passive"))
      (node (ref "U2") (pin "8") (pinfunction "VOUT_8") (pintype "output"))
    )
    (net (code "161") (name "unconnected-(JTAG-Pad12)") (class "Default")
      (node (ref "JTAG") (pin "12") (pinfunction "12_12") (pintype "passive"))
    )
    (net (code "162") (name "unconnected-(JTAG-Pad14)") (class "Default")
      (node (ref "JTAG") (pin "14") (pinfunction "14_14") (pintype "passive"))
    )
    (net (code "163") (name "unconnected-(KME-RA3-Pad2)") (class "Default")
      (node (ref "KME") (pin "2") (pinfunction "RA3_2") (pintype "bidirectional"))
    )
    (net (code "164") (name "unconnected-(KME-RA4-Pad3)") (class "Default")
      (node (ref "KME") (pin "3") (pinfunction "RA4_3") (pintype "bidirectional"))
    )
    (net (code "165") (name "unconnected-(KME-RA7-Pad6)") (class "Default")
      (node (ref "KME") (pin "6") (pinfunction "RA7_6") (pintype "bidirectional"))
    )
    (net (code "166") (name "unconnected-(KME-RC0-Pad8)") (class "Default")
      (node (ref "KME") (pin "8") (pinfunction "RC0_8") (pintype "bidirectional"))
    )
    (net (code "167") (name "unconnected-(KME-RC1-Pad9)") (class "Default")
      (node (ref "KME") (pin "9") (pinfunction "RC1_9") (pintype "bidirectional"))
    )
    (net (code "168") (name "unconnected-(KMW-RB0-Pad18)") (class "Default")
      (node (ref "KMW") (pin "18") (pinfunction "RB0_18") (pintype "bidirectional"))
    )
    (net (code "169") (name "unconnected-(KMW-RB1-Pad19)") (class "Default")
      (node (ref "KMW") (pin "19") (pinfunction "RB1_19") (pintype "bidirectional"))
    )
    (net (code "170") (name "unconnected-(KMW-RB4-Pad22)") (class "Default")
      (node (ref "KMW") (pin "22") (pinfunction "RB4_22") (pintype "bidirectional"))
    )
    (net (code "171") (name "unconnected-(KMW-RC1-Pad9)") (class "Default")
      (node (ref "KMW") (pin "9") (pinfunction "RC1_9") (pintype "bidirectional"))
    )
    (net (code "172") (name "unconnected-(P1-Pad2)") (class "Default")
      (node (ref "P1") (pin "2") (pinfunction "2_2") (pintype "passive"))
    )
    (net (code "173") (name "unconnected-(P1-Pad3)") (class "Default")
      (node (ref "P1") (pin "3") (pinfunction "3_3") (pintype "passive"))
    )
    (net (code "174") (name "unconnected-(P2-Pad2)") (class "Default")
      (node (ref "P2") (pin "2") (pinfunction "2_2") (pintype "passive"))
    )
    (net (code "175") (name "unconnected-(P2-Pad3)") (class "Default")
      (node (ref "P2") (pin "3") (pinfunction "3_3") (pintype "passive"))
    )
    (net (code "176") (name "unconnected-(P3-Pad2)") (class "Default")
      (node (ref "P3") (pin "2") (pinfunction "2_2") (pintype "passive"))
    )
    (net (code "177") (name "unconnected-(P3-Pad3)") (class "Default")
      (node (ref "P3") (pin "3") (pinfunction "3_3") (pintype "passive"))
    )
    (net (code "178") (name "unconnected-(P4-Pad1)") (class "Default")
      (node (ref "P4") (pin "1") (pinfunction "1_1") (pintype "passive"))
    )
    (net (code "179") (name "unconnected-(P4-Pad4)") (class "Default")
      (node (ref "P4") (pin "4") (pinfunction "4_4") (pintype "passive"))
    )
    (net (code "180") (name "unconnected-(P5-Pad1)") (class "Default")
      (node (ref "P5") (pin "1") (pinfunction "1_1") (pintype "passive"))
    )
    (net (code "181") (name "unconnected-(P5-Pad4)") (class "Default")
      (node (ref "P5") (pin "4") (pinfunction "4_4") (pintype "passive"))
    )
    (net (code "182") (name "unconnected-(P6-Pad1)") (class "Default")
      (node (ref "P6") (pin "1") (pinfunction "1_1") (pintype "passive"))
    )
    (net (code "183") (name "unconnected-(P6-Pad4)") (class "Default")
      (node (ref "P6") (pin "4") (pinfunction "4_4") (pintype "passive"))
    )
    (net (code "184") (name "unconnected-(P7-Pad2)") (class "Default")
      (node (ref "P7") (pin "2") (pinfunction "2_2") (pintype "passive"))
    )
    (net (code "185") (name "unconnected-(P7-Pad3)") (class "Default")
      (node (ref "P7") (pin "3") (pinfunction "3_3") (pintype "passive"))
    )
    (net (code "186") (name "unconnected-(P8-Pad2)") (class "Default")
      (node (ref "P8") (pin "2") (pinfunction "2_2") (pintype "passive"))
    )
    (net (code "187") (name "unconnected-(P8-Pad3)") (class "Default")
      (node (ref "P8") (pin "3") (pinfunction "3_3") (pintype "passive"))
    )
    (net (code "188") (name "unconnected-(P9-Pad2)") (class "Default")
      (node (ref "P9") (pin "2") (pinfunction "2_2") (pintype "passive"))
    )
    (net (code "189") (name "unconnected-(P9-Pad3)") (class "Default")
      (node (ref "P9") (pin "3") (pinfunction "3_3") (pintype "passive"))
    )
    (net (code "190") (name "unconnected-(P10-Pad2)") (class "Default")
      (node (ref "P10") (pin "2") (pinfunction "2_2") (pintype "passive"))
    )
    (net (code "191") (name "unconnected-(P10-Pad3)") (class "Default")
      (node (ref "P10") (pin "3") (pinfunction "3_3") (pintype "passive"))
    )
    (net (code "192") (name "unconnected-(P11-Pad2)") (class "Default")
      (node (ref "P11") (pin "2") (pinfunction "2_2") (pintype "passive"))
    )
    (net (code "193") (name "unconnected-(P11-Pad3)") (class "Default")
      (node (ref "P11") (pin "3") (pinfunction "3_3") (pintype "passive"))
    )
    (net (code "194") (name "unconnected-(P12-Pad2)") (class "Default")
      (node (ref "P12") (pin "2") (pinfunction "2_2") (pintype "passive"))
    )
    (net (code "195") (name "unconnected-(P12-Pad3)") (class "Default")
      (node (ref "P12") (pin "3") (pinfunction "3_3") (pintype "passive"))
    )
    (net (code "196") (name "unconnected-(P13-Pad2)") (class "Default")
      (node (ref "P13") (pin "2") (pinfunction "2_2") (pintype "passive"))
    )
    (net (code "197") (name "unconnected-(P13-Pad3)") (class "Default")
      (node (ref "P13") (pin "3") (pinfunction "3_3") (pintype "passive"))
    )
    (net (code "198") (name "unconnected-(RESET-Pad2)") (class "Default")
      (node (ref "RESET") (pin "2") (pinfunction "2_2") (pintype "passive"))
    )
    (net (code "199") (name "unconnected-(RESET-Pad3)") (class "Default")
      (node (ref "RESET") (pin "3") (pinfunction "3_3") (pintype "passive"))
    )
    (net (code "200") (name "~{MCLR}") (class "Default")
      (node (ref "C54") (pin "1") (pinfunction "1_1") (pintype "passive"))
      (node (ref "ICSP") (pin "1") (pinfunction "1_1") (pintype "passive"))
      (node (ref "R48") (pin "2") (pinfunction "2_2") (pintype "passive"))
      (node (ref "R49") (pin "1") (pinfunction "1_1") (pintype "passive"))
      (node (ref "U1") (pin "15") (pinfunction "~{MCLR}_15") (pintype "bidirectional"))
    )
    (net (code "201") (name "~{SS6}") (class "Default")
      (node (ref "TFT") (pin "38") (pinfunction "/CS_38") (pintype "bidirectional"))
      (node (ref "U1") (pin "6") (pinfunction "PMA6_6") (pintype "bidirectional"))
      (node (ref "U1") (pin "68") (pinfunction "PMA15_68") (pintype "bidirectional"))
    )
  )
)
